# H743ZI_SD_LCD_DRAM_Dev.net
KiCad netlist of a schematic drawn in Altium Designer
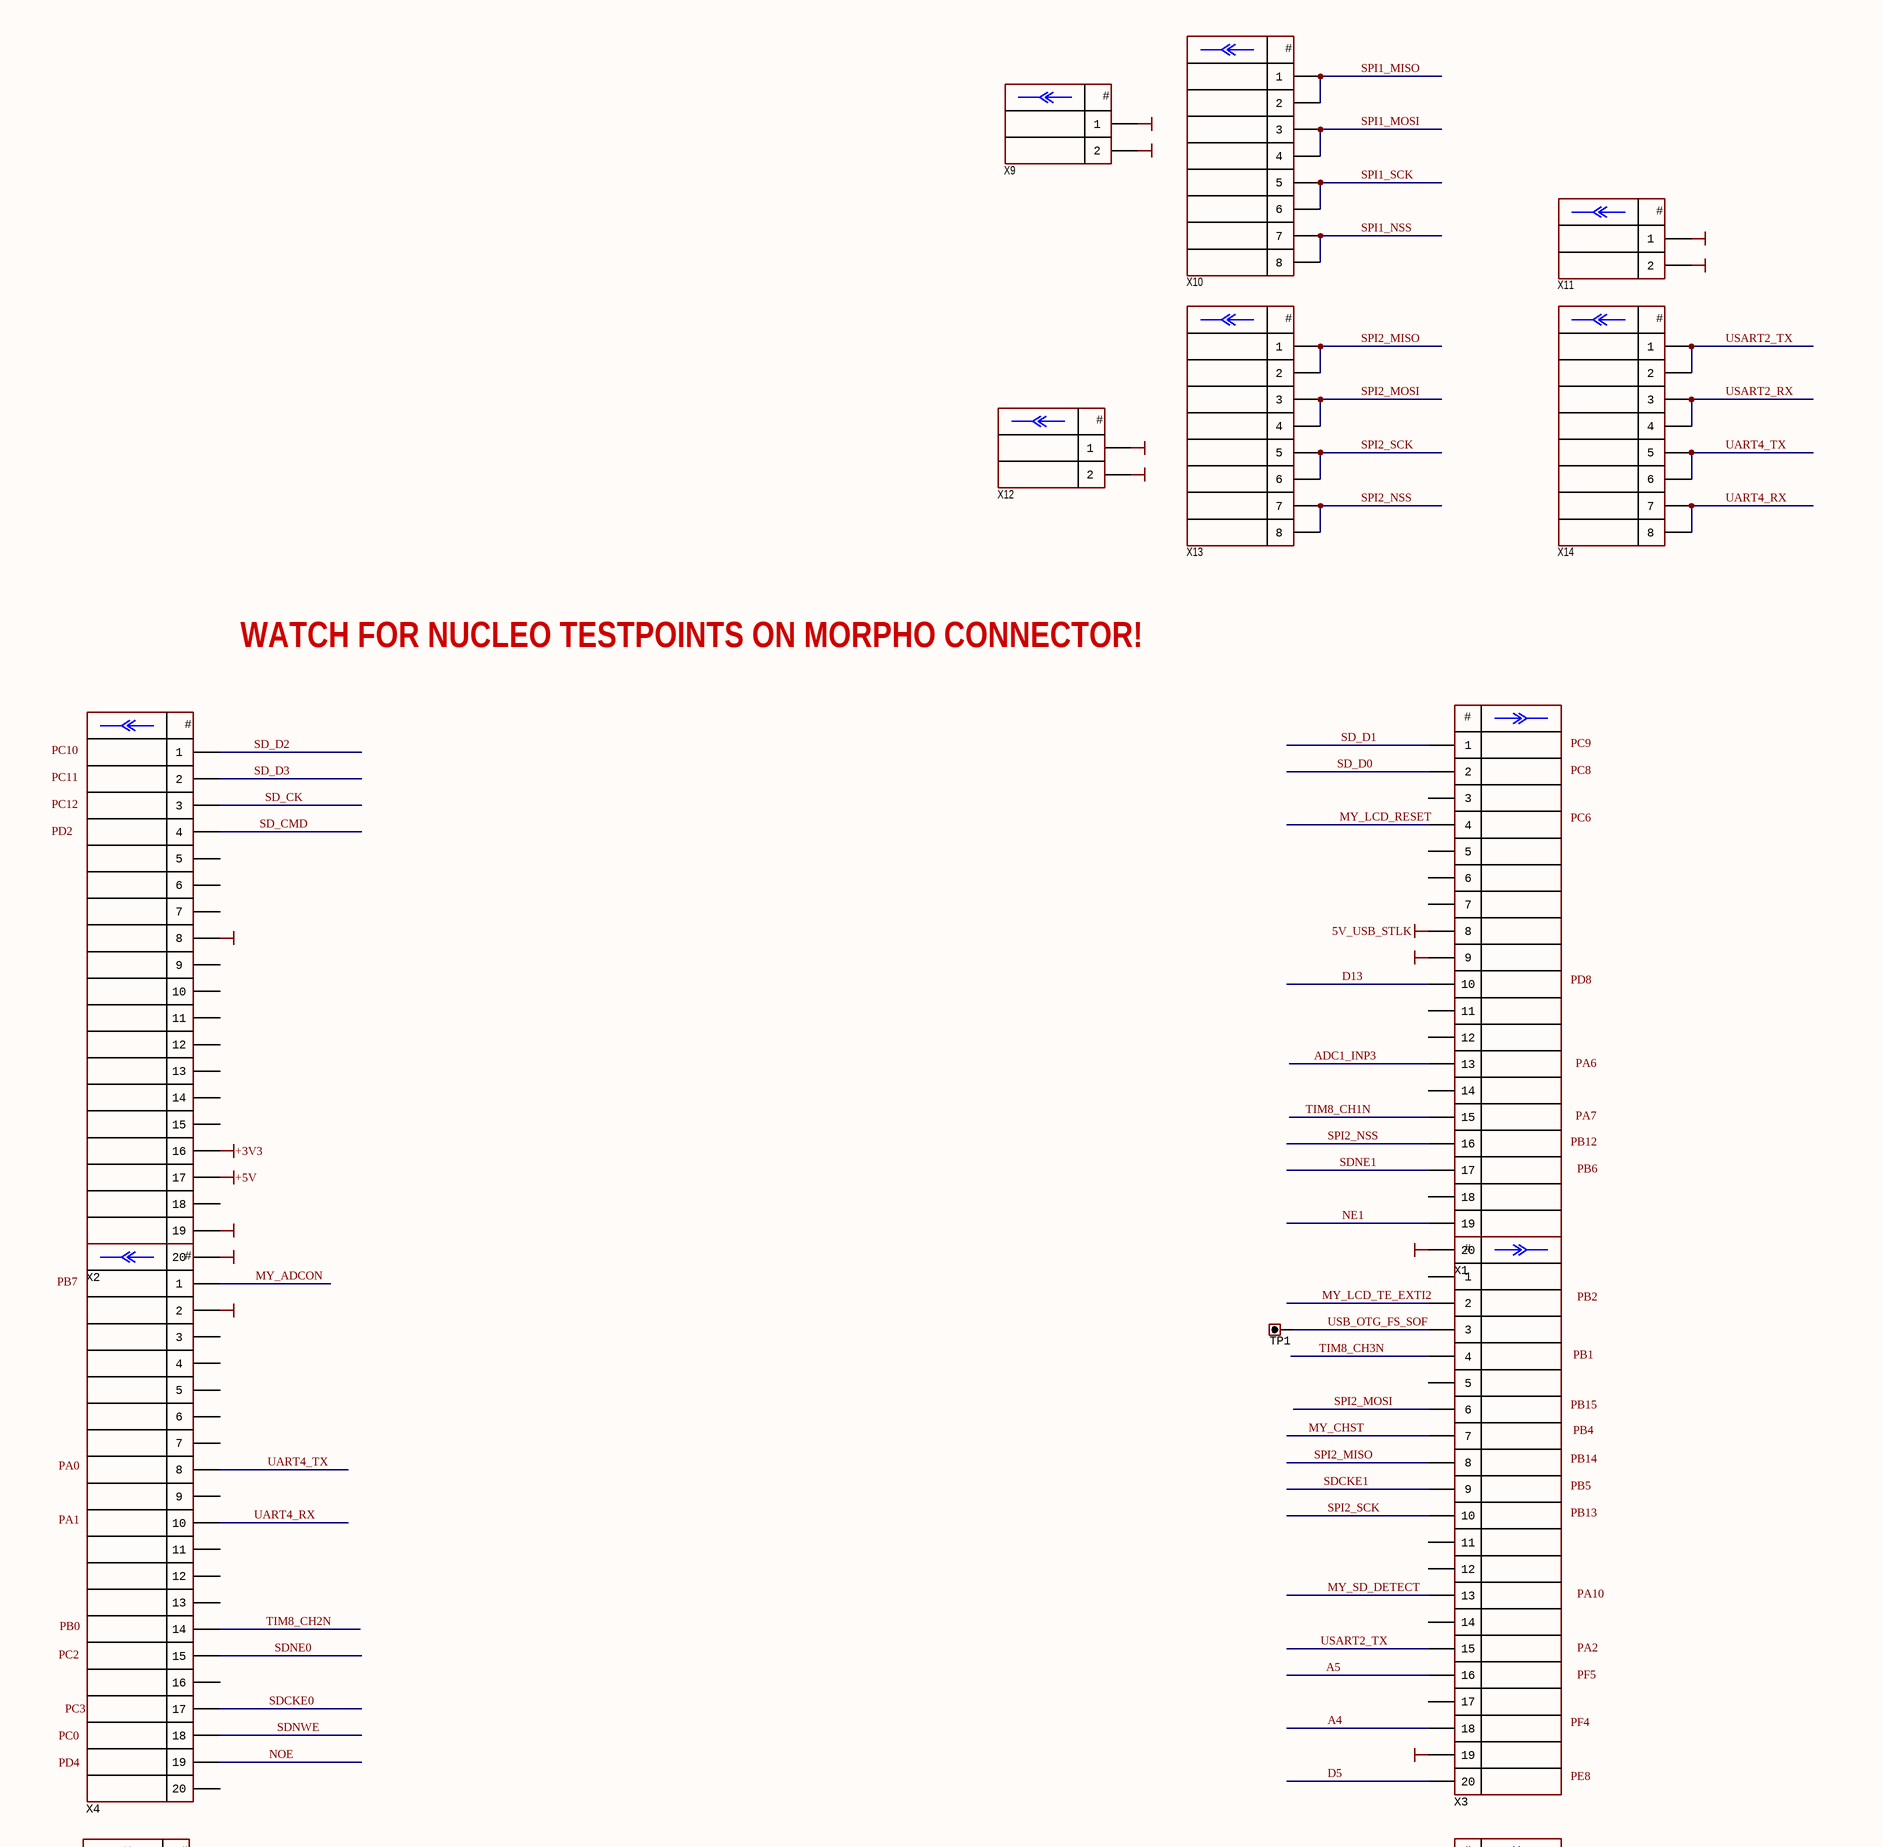
[diagram p0: H743ZI_SD_LCD_DRAM_Dev.SchDoc, top left]
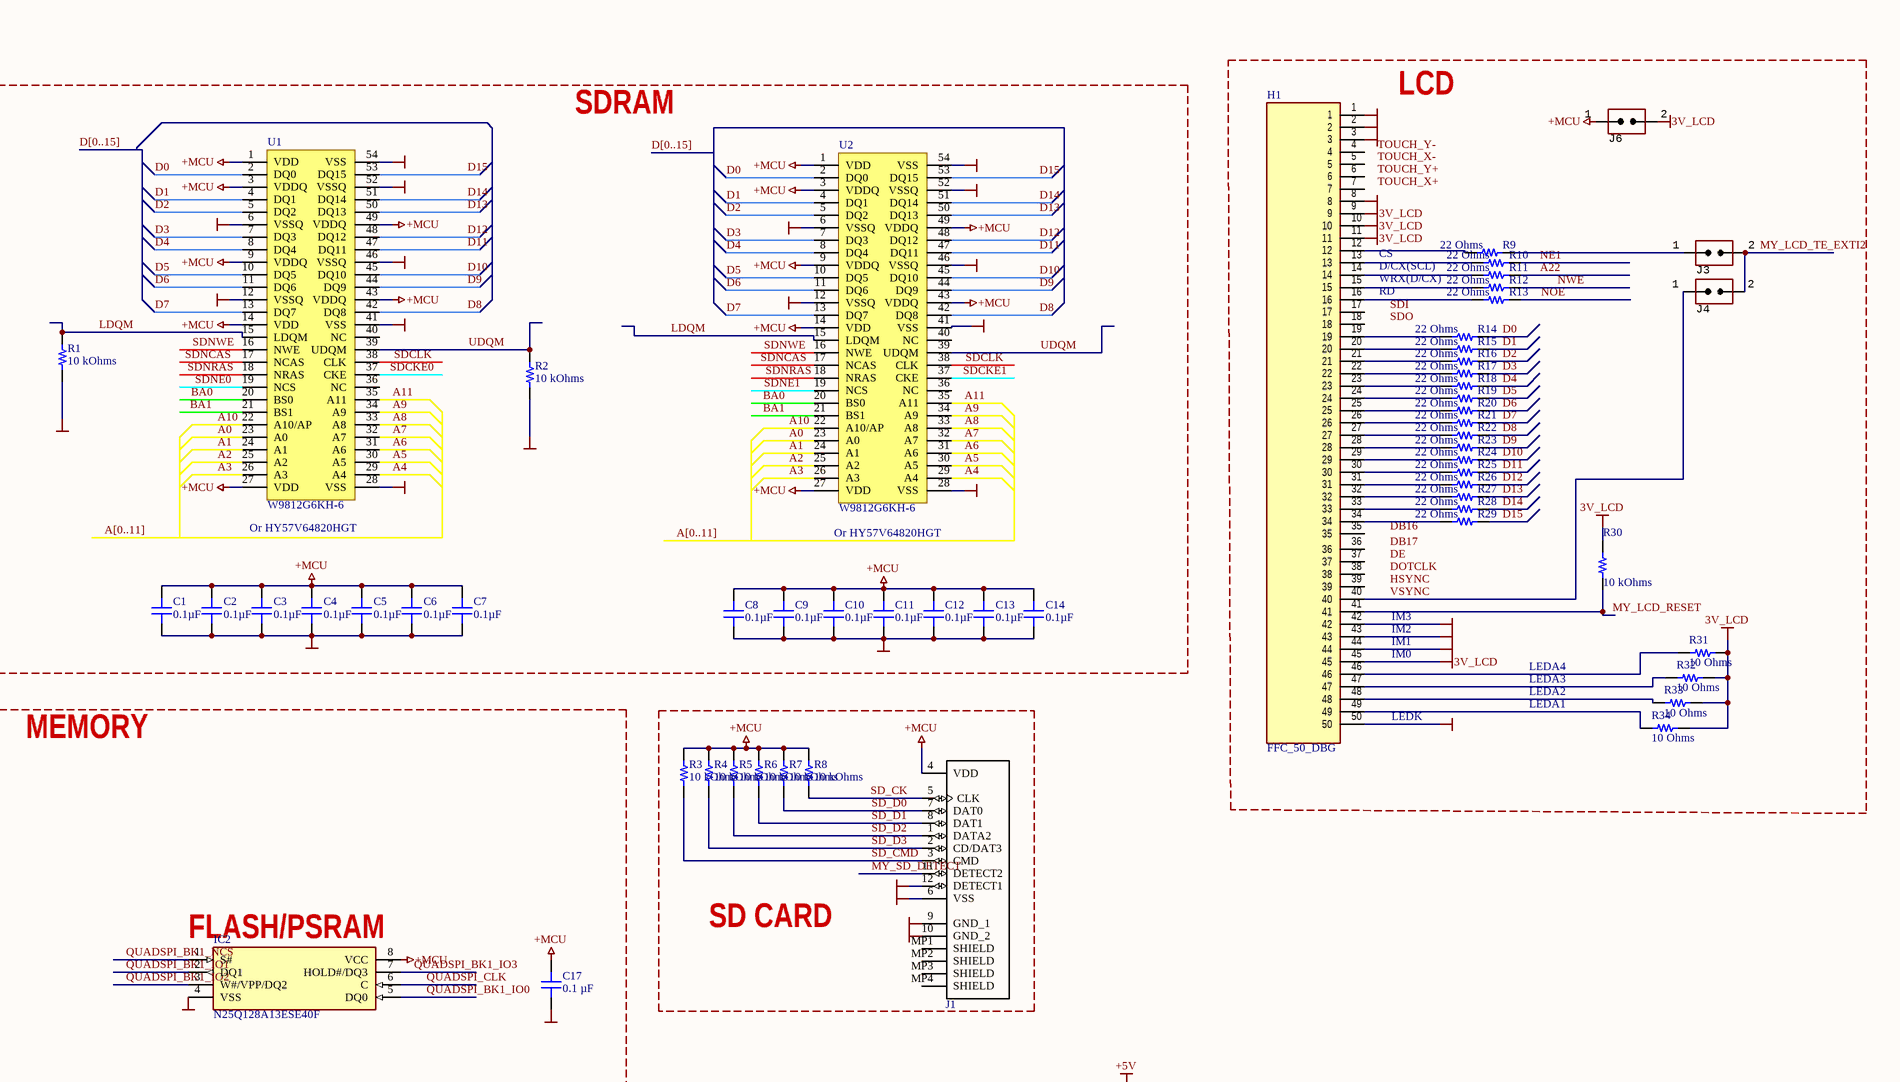
[diagram p1: H743ZI_SD_LCD_DRAM_Dev.SchDoc, top right]
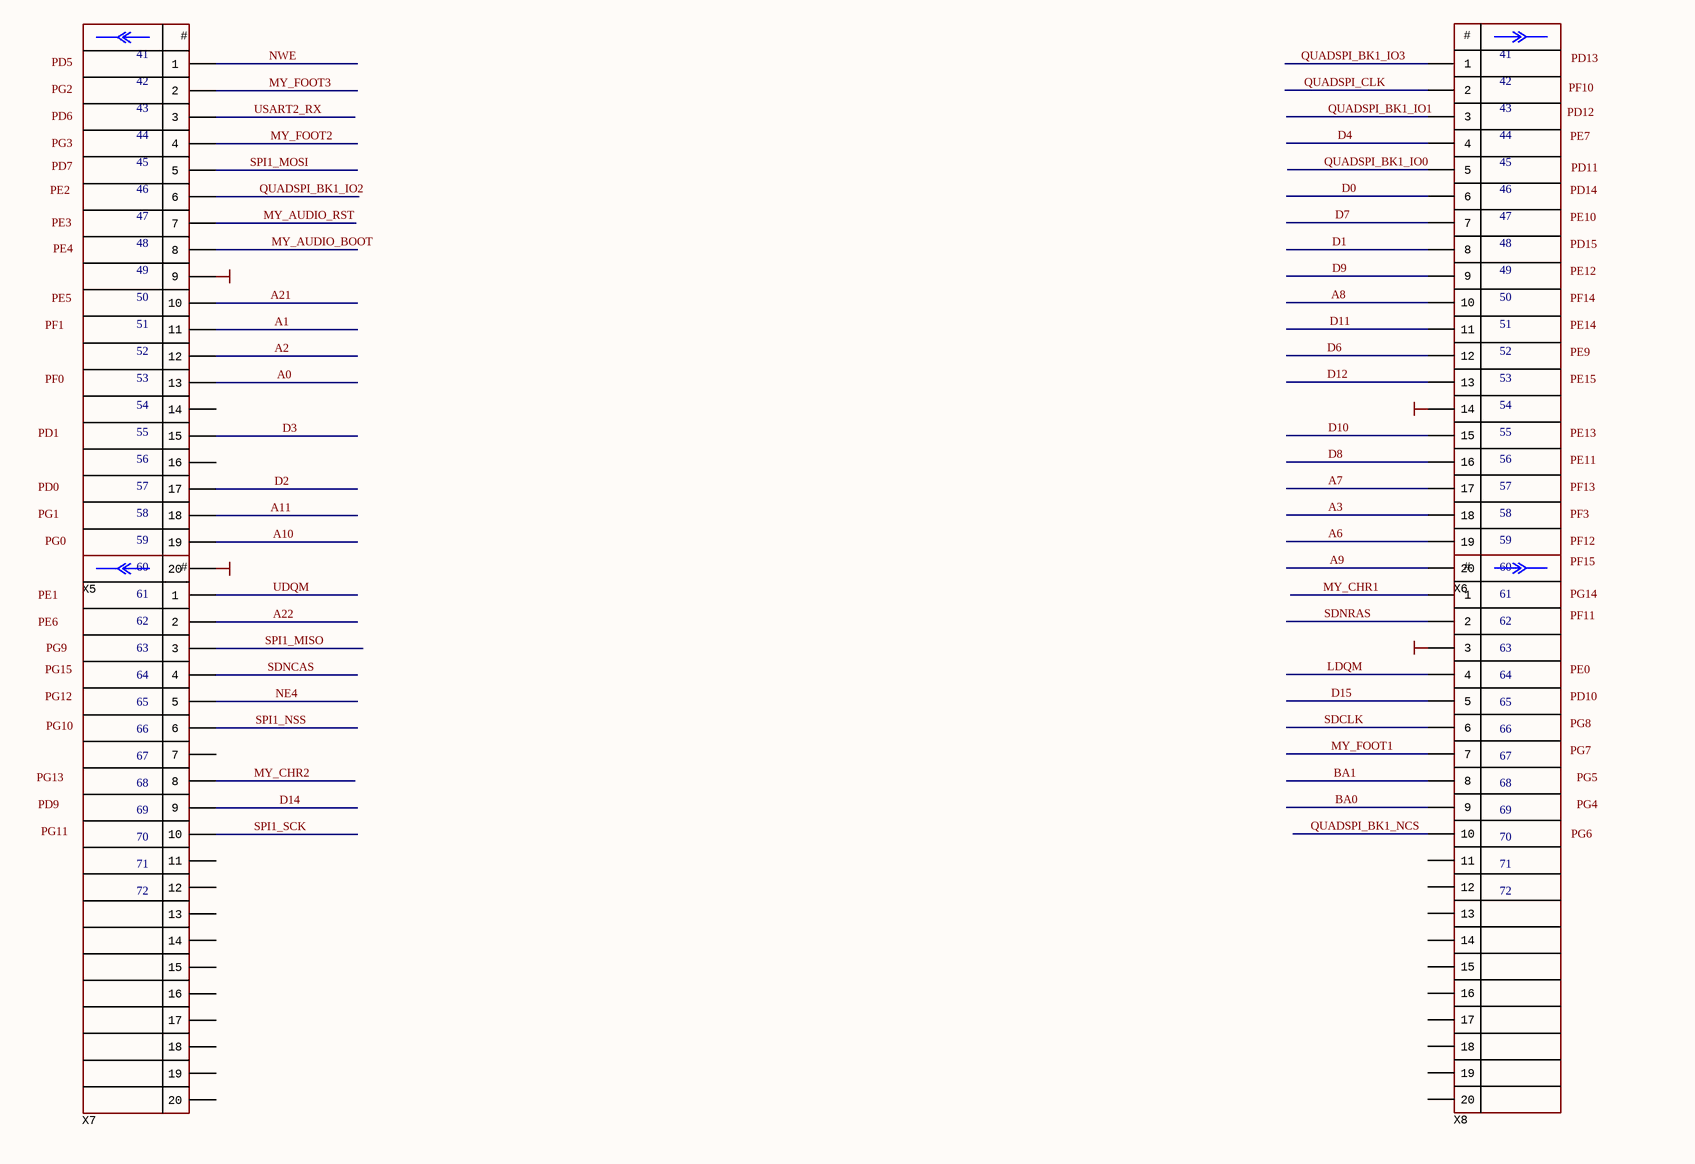
[diagram p2: H743ZI_SD_LCD_DRAM_Dev.SchDoc, bottom left]
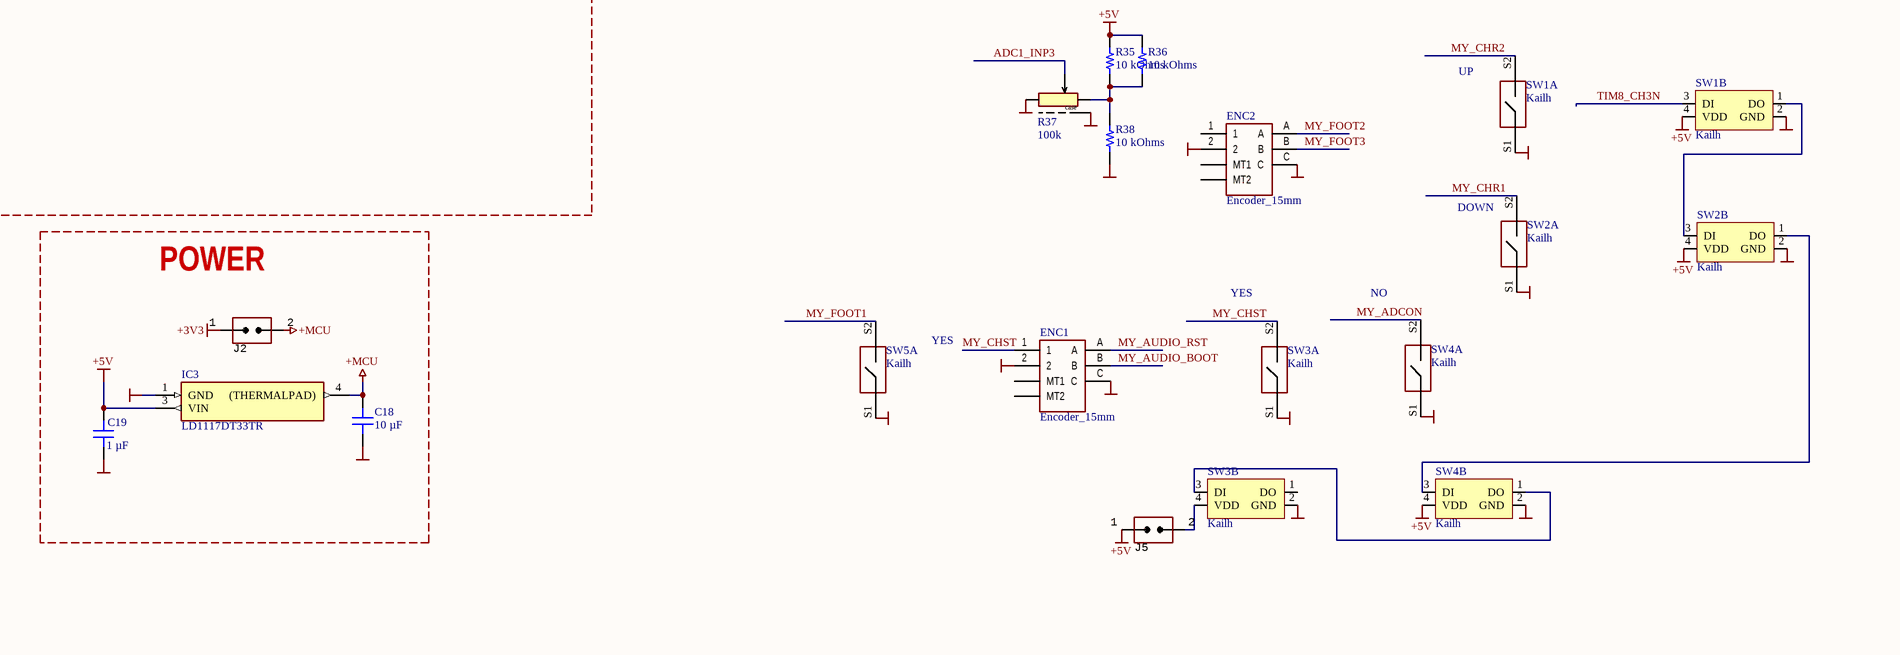
[diagram p3: H743ZI_SD_LCD_DRAM_Dev.SchDoc, bottom right]

(export (version "E")
  (design (tool "Eeschema 10.0.6"))
  (components
    (comp (ref "C1")
      (value "0.1µF")
      (footprint "CAP 0402_1005")
      (description "CAP CER 0.1UF 16V X7R 0402")
      (fields (field (name "PART NUMBER") "C0402C104K4RACAUTO") (field (name "MANUFACTURER") "KEMET"))
      (libsource (lib "Celestial Altium Library - altium_library") (part "Capacitor"))
    )
    (comp (ref "C2")
      (value "0.1µF")
      (footprint "CAP 0402_1005")
      (description "CAP CER 0.1UF 16V X7R 0402")
      (fields (field (name "PART NUMBER") "C0402C104K4RACAUTO") (field (name "MANUFACTURER") "KEMET"))
      (libsource (lib "Celestial Altium Library - altium_library") (part "Capacitor"))
    )
    (comp (ref "C3")
      (value "0.1µF")
      (footprint "CAP 0402_1005")
      (description "CAP CER 0.1UF 16V X7R 0402")
      (fields (field (name "PART NUMBER") "C0402C104K4RACAUTO") (field (name "MANUFACTURER") "KEMET"))
      (libsource (lib "Celestial Altium Library - altium_library") (part "Capacitor"))
    )
    (comp (ref "C4")
      (value "0.1µF")
      (footprint "CAP 0402_1005")
      (description "CAP CER 0.1UF 16V X7R 0402")
      (fields (field (name "PART NUMBER") "C0402C104K4RACAUTO") (field (name "MANUFACTURER") "KEMET"))
      (libsource (lib "Celestial Altium Library - altium_library") (part "Capacitor"))
    )
    (comp (ref "C5")
      (value "0.1µF")
      (footprint "CAP 0402_1005")
      (description "CAP CER 0.1UF 16V X7R 0402")
      (fields (field (name "PART NUMBER") "C0402C104K4RACAUTO") (field (name "MANUFACTURER") "KEMET"))
      (libsource (lib "Celestial Altium Library - altium_library") (part "Capacitor"))
    )
    (comp (ref "C6")
      (value "0.1µF")
      (footprint "CAP 0402_1005")
      (description "CAP CER 0.1UF 16V X7R 0402")
      (fields (field (name "PART NUMBER") "C0402C104K4RACAUTO") (field (name "MANUFACTURER") "KEMET"))
      (libsource (lib "Celestial Altium Library - altium_library") (part "Capacitor"))
    )
    (comp (ref "C7")
      (value "0.1µF")
      (footprint "CAP 0402_1005")
      (description "CAP CER 0.1UF 16V X7R 0402")
      (fields (field (name "PART NUMBER") "C0402C104K4RACAUTO") (field (name "MANUFACTURER") "KEMET"))
      (libsource (lib "Celestial Altium Library - altium_library") (part "Capacitor"))
    )
    (comp (ref "C8")
      (value "0.1µF")
      (footprint "CAP 0402_1005")
      (description "CAP CER 0.1UF 16V X7R 0402")
      (fields (field (name "PART NUMBER") "C0402C104K4RACAUTO") (field (name "MANUFACTURER") "KEMET"))
      (libsource (lib "Celestial Altium Library - altium_library") (part "Capacitor"))
    )
    (comp (ref "C9")
      (value "0.1µF")
      (footprint "CAP 0402_1005")
      (description "CAP CER 0.1UF 16V X7R 0402")
      (fields (field (name "PART NUMBER") "C0402C104K4RACAUTO") (field (name "MANUFACTURER") "KEMET"))
      (libsource (lib "Celestial Altium Library - altium_library") (part "Capacitor"))
    )
    (comp (ref "C10")
      (value "0.1µF")
      (footprint "CAP 0402_1005")
      (description "CAP CER 0.1UF 16V X7R 0402")
      (fields (field (name "PART NUMBER") "C0402C104K4RACAUTO") (field (name "MANUFACTURER") "KEMET"))
      (libsource (lib "Celestial Altium Library - altium_library") (part "Capacitor"))
    )
    (comp (ref "C11")
      (value "0.1µF")
      (footprint "CAP 0402_1005")
      (description "CAP CER 0.1UF 16V X7R 0402")
      (fields (field (name "PART NUMBER") "C0402C104K4RACAUTO") (field (name "MANUFACTURER") "KEMET"))
      (libsource (lib "Celestial Altium Library - altium_library") (part "Capacitor"))
    )
    (comp (ref "C12")
      (value "0.1µF")
      (footprint "CAP 0402_1005")
      (description "CAP CER 0.1UF 16V X7R 0402")
      (fields (field (name "PART NUMBER") "C0402C104K4RACAUTO") (field (name "MANUFACTURER") "KEMET"))
      (libsource (lib "Celestial Altium Library - altium_library") (part "Capacitor"))
    )
    (comp (ref "C13")
      (value "0.1µF")
      (footprint "CAP 0402_1005")
      (description "CAP CER 0.1UF 16V X7R 0402")
      (fields (field (name "PART NUMBER") "C0402C104K4RACAUTO") (field (name "MANUFACTURER") "KEMET"))
      (libsource (lib "Celestial Altium Library - altium_library") (part "Capacitor"))
    )
    (comp (ref "C14")
      (value "0.1µF")
      (footprint "CAP 0402_1005")
      (description "CAP CER 0.1UF 16V X7R 0402")
      (fields (field (name "PART NUMBER") "C0402C104K4RACAUTO") (field (name "MANUFACTURER") "KEMET"))
      (libsource (lib "Celestial Altium Library - altium_library") (part "Capacitor"))
    )
    (comp (ref "C17")
      (value "0.1 µF")
      (footprint "CAP 0603_1608")
      (description "CAP CER 0.1UF 50V X7R 0603")
      (fields (field (name "PART NUMBER") "C0603C104K5RAC7411") (field (name "MANUFACTURER") "KEMET"))
      (libsource (lib "Celestial Altium Library - altium_library") (part "Capacitor"))
    )
    (comp (ref "C18")
      (value "10 µF")
      (footprint "CAP 0805_2012")
      (description "CAP CER 10UF 10V X5R 0805")
      (fields (field (name "PART NUMBER") "C0805C106K8PAC7800") (field (name "MANUFACTURER") "KEMET"))
      (libsource (lib "Celestial Altium Library - altium_library") (part "Capacitor"))
    )
    (comp (ref "C19")
      (value "1 µF")
      (footprint "CAP 0805_2012")
      (description "CAP CER 1UF 16V X7R 0805")
      (fields (field (name "PART NUMBER") "C0805C105K4RAC7800") (field (name "MANUFACTURER") "KEMET"))
      (libsource (lib "Celestial Altium Library - altium_library") (part "Capacitor"))
    )
    (comp (ref "ENC1")
      (value "Encoder_15mm")
      (footprint "ProtoStack_H750VBT:EC11_15mm")
      (libsource (lib "ProtoStack_H750VBT") (part "Encoder_15mm"))
    )
    (comp (ref "ENC2")
      (value "Encoder_15mm")
      (footprint "ProtoStack_H750VBT:EC11_15mm")
      (libsource (lib "ProtoStack_H750VBT") (part "Encoder_15mm"))
    )
    (comp (ref "H1")
      (value "FFC_50_DBG")
      (footprint "ProtoStack_H750VBT:FFC_50_DBG")
      (libsource (lib "ProtoStack_H750VBT") (part "FFC_50_DBG"))
    )
    (comp (ref "IC2")
      (value "N25Q128A13ESE40F")
      (footprint "SOIC127P790X216-8N")
      (description "Integrated Circuit")
      (fields (field (name "MOUSER PART NUMBER") "340-182267"))
      (libsource (lib "ProtoStack_H750VBT") (part "N25Q128A13ESE40F"))
    )
    (comp (ref "IC3")
      (value "LD1117DT33TR")
      (footprint "ProtoStack_H750VBT:TO228P972X240-3N")
      (description "Integrated Circuit")
      (fields (field (name "MOUSER PART NUMBER") "511-LD1117DT33-TR"))
      (libsource (lib "ProtoStack_H750VBT") (part "LD1117DT33TR"))
    )
    (comp (ref "J1")
      (value "SCHA4B0400")
      (footprint "ProtoStack_H750VBT:SCHA4B0400")
      (description "SD card Connector")
      (fields (field (name "MOUSER PART NUMBER") "688-SCHA4B0400"))
      (libsource (lib "ProtoStack_H750VBT") (part "SCHA4B0400"))
    )
    (comp (ref "J2")
      (value "~")
      (footprint "CON: JUMPER x1")
      (libsource (lib "connector") (part "Jumper_single"))
    )
    (comp (ref "J3")
      (value "~")
      (footprint "CON: JUMPER x1")
      (libsource (lib "connector") (part "Jumper_single"))
    )
    (comp (ref "J4")
      (value "~")
      (footprint "CON: JUMPER x1")
      (libsource (lib "connector") (part "Jumper_single"))
    )
    (comp (ref "J5")
      (value "~")
      (footprint "CON: JUMPER x1")
      (libsource (lib "connector") (part "Jumper_single"))
    )
    (comp (ref "J6")
      (value "~")
      (footprint "CON: JUMPER x1")
      (libsource (lib "connector") (part "Jumper_single"))
    )
    (comp (ref "R1")
      (value "10 kOhms")
      (footprint "RES 0603_1608")
      (description "RES SMD 10K OHM 1% 1/10W 0603")
      (fields
        (field (name "PART NUMBER") "ERJ-3EKF1002V")
        (field (name "MANUFACTURER") "Panasonic Electronic Components")
      )
      (libsource (lib "Celestial Altium Library - altium_library") (part "Resistor"))
    )
    (comp (ref "R2")
      (value "10 kOhms")
      (footprint "RES 0603_1608")
      (description "RES SMD 10K OHM 1% 1/10W 0603")
      (fields
        (field (name "PART NUMBER") "ERJ-3EKF1002V")
        (field (name "MANUFACTURER") "Panasonic Electronic Components")
      )
      (libsource (lib "Celestial Altium Library - altium_library") (part "Resistor"))
    )
    (comp (ref "R3")
      (value "10 kOhms")
      (footprint "RES 0603_1608")
      (description "RES SMD 10K OHM 1% 1/10W 0603")
      (fields
        (field (name "PART NUMBER") "ERJ-3EKF1002V")
        (field (name "MANUFACTURER") "Panasonic Electronic Components")
      )
      (libsource (lib "Celestial Altium Library - altium_library") (part "Resistor"))
    )
    (comp (ref "R4")
      (value "10 kOhms")
      (footprint "RES 0603_1608")
      (description "RES SMD 10K OHM 1% 1/10W 0603")
      (fields
        (field (name "PART NUMBER") "ERJ-3EKF1002V")
        (field (name "MANUFACTURER") "Panasonic Electronic Components")
      )
      (libsource (lib "Celestial Altium Library - altium_library") (part "Resistor"))
    )
    (comp (ref "R5")
      (value "10 kOhms")
      (footprint "RES 0603_1608")
      (description "RES SMD 10K OHM 1% 1/10W 0603")
      (fields
        (field (name "PART NUMBER") "ERJ-3EKF1002V")
        (field (name "MANUFACTURER") "Panasonic Electronic Components")
      )
      (libsource (lib "Celestial Altium Library - altium_library") (part "Resistor"))
    )
    (comp (ref "R6")
      (value "10 kOhms")
      (footprint "RES 0603_1608")
      (description "RES SMD 10K OHM 1% 1/10W 0603")
      (fields
        (field (name "PART NUMBER") "ERJ-3EKF1002V")
        (field (name "MANUFACTURER") "Panasonic Electronic Components")
      )
      (libsource (lib "Celestial Altium Library - altium_library") (part "Resistor"))
    )
    (comp (ref "R7")
      (value "10 kOhms")
      (footprint "RES 0603_1608")
      (description "RES SMD 10K OHM 1% 1/10W 0603")
      (fields
        (field (name "PART NUMBER") "ERJ-3EKF1002V")
        (field (name "MANUFACTURER") "Panasonic Electronic Components")
      )
      (libsource (lib "Celestial Altium Library - altium_library") (part "Resistor"))
    )
    (comp (ref "R8")
      (value "10 kOhms")
      (footprint "RES 0603_1608")
      (description "RES SMD 10K OHM 1% 1/10W 0603")
      (fields
        (field (name "PART NUMBER") "ERJ-3EKF1002V")
        (field (name "MANUFACTURER") "Panasonic Electronic Components")
      )
      (libsource (lib "Celestial Altium Library - altium_library") (part "Resistor"))
    )
    (comp (ref "R9")
      (value "22 Ohms")
      (footprint "RES 0402_1005")
      (description "RES 22 OHM 5% 1/16W 0402")
      (fields
        (field (name "PART NUMBER") "RMCF0402JT22R0")
        (field (name "MANUFACTURER") "Stackpole Electronics Inc")
      )
      (libsource (lib "Celestial Altium Library - altium_library") (part "Resistor"))
    )
    (comp (ref "R10")
      (value "22 Ohms")
      (footprint "RES 0402_1005")
      (description "RES 22 OHM 5% 1/16W 0402")
      (fields
        (field (name "PART NUMBER") "RMCF0402JT22R0")
        (field (name "MANUFACTURER") "Stackpole Electronics Inc")
      )
      (libsource (lib "Celestial Altium Library - altium_library") (part "Resistor"))
    )
    (comp (ref "R11")
      (value "22 Ohms")
      (footprint "RES 0402_1005")
      (description "RES 22 OHM 5% 1/16W 0402")
      (fields
        (field (name "PART NUMBER") "RMCF0402JT22R0")
        (field (name "MANUFACTURER") "Stackpole Electronics Inc")
      )
      (libsource (lib "Celestial Altium Library - altium_library") (part "Resistor"))
    )
    (comp (ref "R12")
      (value "22 Ohms")
      (footprint "RES 0402_1005")
      (description "RES 22 OHM 5% 1/16W 0402")
      (fields
        (field (name "PART NUMBER") "RMCF0402JT22R0")
        (field (name "MANUFACTURER") "Stackpole Electronics Inc")
      )
      (libsource (lib "Celestial Altium Library - altium_library") (part "Resistor"))
    )
    (comp (ref "R13")
      (value "22 Ohms")
      (footprint "RES 0402_1005")
      (description "RES 22 OHM 5% 1/16W 0402")
      (fields
        (field (name "PART NUMBER") "RMCF0402JT22R0")
        (field (name "MANUFACTURER") "Stackpole Electronics Inc")
      )
      (libsource (lib "Celestial Altium Library - altium_library") (part "Resistor"))
    )
    (comp (ref "R14")
      (value "22 Ohms")
      (footprint "RES 0402_1005")
      (description "RES 22 OHM 5% 1/16W 0402")
      (fields
        (field (name "PART NUMBER") "RMCF0402JT22R0")
        (field (name "MANUFACTURER") "Stackpole Electronics Inc")
      )
      (libsource (lib "Celestial Altium Library - altium_library") (part "Resistor"))
    )
    (comp (ref "R15")
      (value "22 Ohms")
      (footprint "RES 0402_1005")
      (description "RES 22 OHM 5% 1/16W 0402")
      (fields
        (field (name "PART NUMBER") "RMCF0402JT22R0")
        (field (name "MANUFACTURER") "Stackpole Electronics Inc")
      )
      (libsource (lib "Celestial Altium Library - altium_library") (part "Resistor"))
    )
    (comp (ref "R16")
      (value "22 Ohms")
      (footprint "RES 0402_1005")
      (description "RES 22 OHM 5% 1/16W 0402")
      (fields
        (field (name "PART NUMBER") "RMCF0402JT22R0")
        (field (name "MANUFACTURER") "Stackpole Electronics Inc")
      )
      (libsource (lib "Celestial Altium Library - altium_library") (part "Resistor"))
    )
    (comp (ref "R17")
      (value "22 Ohms")
      (footprint "RES 0402_1005")
      (description "RES 22 OHM 5% 1/16W 0402")
      (fields
        (field (name "PART NUMBER") "RMCF0402JT22R0")
        (field (name "MANUFACTURER") "Stackpole Electronics Inc")
      )
      (libsource (lib "Celestial Altium Library - altium_library") (part "Resistor"))
    )
    (comp (ref "R18")
      (value "22 Ohms")
      (footprint "RES 0402_1005")
      (description "RES 22 OHM 5% 1/16W 0402")
      (fields
        (field (name "PART NUMBER") "RMCF0402JT22R0")
        (field (name "MANUFACTURER") "Stackpole Electronics Inc")
      )
      (libsource (lib "Celestial Altium Library - altium_library") (part "Resistor"))
    )
    (comp (ref "R19")
      (value "22 Ohms")
      (footprint "RES 0402_1005")
      (description "RES 22 OHM 5% 1/16W 0402")
      (fields
        (field (name "PART NUMBER") "RMCF0402JT22R0")
        (field (name "MANUFACTURER") "Stackpole Electronics Inc")
      )
      (libsource (lib "Celestial Altium Library - altium_library") (part "Resistor"))
    )
    (comp (ref "R20")
      (value "22 Ohms")
      (footprint "RES 0402_1005")
      (description "RES 22 OHM 5% 1/16W 0402")
      (fields
        (field (name "PART NUMBER") "RMCF0402JT22R0")
        (field (name "MANUFACTURER") "Stackpole Electronics Inc")
      )
      (libsource (lib "Celestial Altium Library - altium_library") (part "Resistor"))
    )
    (comp (ref "R21")
      (value "22 Ohms")
      (footprint "RES 0402_1005")
      (description "RES 22 OHM 5% 1/16W 0402")
      (fields
        (field (name "PART NUMBER") "RMCF0402JT22R0")
        (field (name "MANUFACTURER") "Stackpole Electronics Inc")
      )
      (libsource (lib "Celestial Altium Library - altium_library") (part "Resistor"))
    )
    (comp (ref "R22")
      (value "22 Ohms")
      (footprint "RES 0402_1005")
      (description "RES 22 OHM 5% 1/16W 0402")
      (fields
        (field (name "PART NUMBER") "RMCF0402JT22R0")
        (field (name "MANUFACTURER") "Stackpole Electronics Inc")
      )
      (libsource (lib "Celestial Altium Library - altium_library") (part "Resistor"))
    )
    (comp (ref "R23")
      (value "22 Ohms")
      (footprint "RES 0402_1005")
      (description "RES 22 OHM 5% 1/16W 0402")
      (fields
        (field (name "PART NUMBER") "RMCF0402JT22R0")
        (field (name "MANUFACTURER") "Stackpole Electronics Inc")
      )
      (libsource (lib "Celestial Altium Library - altium_library") (part "Resistor"))
    )
    (comp (ref "R24")
      (value "22 Ohms")
      (footprint "RES 0402_1005")
      (description "RES 22 OHM 5% 1/16W 0402")
      (fields
        (field (name "PART NUMBER") "RMCF0402JT22R0")
        (field (name "MANUFACTURER") "Stackpole Electronics Inc")
      )
      (libsource (lib "Celestial Altium Library - altium_library") (part "Resistor"))
    )
    (comp (ref "R25")
      (value "22 Ohms")
      (footprint "RES 0402_1005")
      (description "RES 22 OHM 5% 1/16W 0402")
      (fields
        (field (name "PART NUMBER") "RMCF0402JT22R0")
        (field (name "MANUFACTURER") "Stackpole Electronics Inc")
      )
      (libsource (lib "Celestial Altium Library - altium_library") (part "Resistor"))
    )
    (comp (ref "R26")
      (value "22 Ohms")
      (footprint "RES 0402_1005")
      (description "RES 22 OHM 5% 1/16W 0402")
      (fields
        (field (name "PART NUMBER") "RMCF0402JT22R0")
        (field (name "MANUFACTURER") "Stackpole Electronics Inc")
      )
      (libsource (lib "Celestial Altium Library - altium_library") (part "Resistor"))
    )
    (comp (ref "R27")
      (value "22 Ohms")
      (footprint "RES 0402_1005")
      (description "RES 22 OHM 5% 1/16W 0402")
      (fields
        (field (name "PART NUMBER") "RMCF0402JT22R0")
        (field (name "MANUFACTURER") "Stackpole Electronics Inc")
      )
      (libsource (lib "Celestial Altium Library - altium_library") (part "Resistor"))
    )
    (comp (ref "R28")
      (value "22 Ohms")
      (footprint "RES 0402_1005")
      (description "RES 22 OHM 5% 1/16W 0402")
      (fields
        (field (name "PART NUMBER") "RMCF0402JT22R0")
        (field (name "MANUFACTURER") "Stackpole Electronics Inc")
      )
      (libsource (lib "Celestial Altium Library - altium_library") (part "Resistor"))
    )
    (comp (ref "R29")
      (value "22 Ohms")
      (footprint "RES 0402_1005")
      (description "RES 22 OHM 5% 1/16W 0402")
      (fields
        (field (name "PART NUMBER") "RMCF0402JT22R0")
        (field (name "MANUFACTURER") "Stackpole Electronics Inc")
      )
      (libsource (lib "Celestial Altium Library - altium_library") (part "Resistor"))
    )
    (comp (ref "R30")
      (value "10 kOhms")
      (footprint "RES 0603_1608")
      (description "RES SMD 10K OHM 1% 1/10W 0603")
      (fields
        (field (name "PART NUMBER") "ERJ-3EKF1002V")
        (field (name "MANUFACTURER") "Panasonic Electronic Components")
      )
      (libsource (lib "Celestial Altium Library - altium_library") (part "Resistor"))
    )
    (comp (ref "R31")
      (value "10 Ohms")
      (footprint "RES 0603_1608")
      (description "RES SMD 10 OHM 1% 1/3W 0603")
      (fields
        (field (name "PART NUMBER") "ERJ-PA3F10R0V")
        (field (name "MANUFACTURER") "Panasonic Electronic Components")
      )
      (libsource (lib "Celestial Altium Library - altium_library") (part "Resistor"))
    )
    (comp (ref "R32")
      (value "10 Ohms")
      (footprint "RES 0603_1608")
      (description "RES SMD 10 OHM 1% 1/3W 0603")
      (fields
        (field (name "PART NUMBER") "ERJ-PA3F10R0V")
        (field (name "MANUFACTURER") "Panasonic Electronic Components")
      )
      (libsource (lib "Celestial Altium Library - altium_library") (part "Resistor"))
    )
    (comp (ref "R33")
      (value "10 Ohms")
      (footprint "RES 0603_1608")
      (description "RES SMD 10 OHM 1% 1/3W 0603")
      (fields
        (field (name "PART NUMBER") "ERJ-PA3F10R0V")
        (field (name "MANUFACTURER") "Panasonic Electronic Components")
      )
      (libsource (lib "Celestial Altium Library - altium_library") (part "Resistor"))
    )
    (comp (ref "R34")
      (value "10 Ohms")
      (footprint "RES 0603_1608")
      (description "RES SMD 10 OHM 1% 1/3W 0603")
      (fields
        (field (name "PART NUMBER") "ERJ-PA3F10R0V")
        (field (name "MANUFACTURER") "Panasonic Electronic Components")
      )
      (libsource (lib "Celestial Altium Library - altium_library") (part "Resistor"))
    )
    (comp (ref "R35")
      (value "10 kOhms")
      (footprint "RES 0603_1608")
      (description "RES SMD 10K OHM 1% 1/10W 0603")
      (fields (field (name "PART NUMBER") "ERJ-3EKF1002V"))
      (libsource (lib "Celestial Altium Library - altium_library") (part "Resistor"))
    )
    (comp (ref "R36")
      (value "10 kOhms")
      (footprint "RES 0603_1608")
      (description "RES SMD 10K OHM 1% 1/10W 0603")
      (fields (field (name "PART NUMBER") "ERJ-3EKF1002V"))
      (libsource (lib "Celestial Altium Library - altium_library") (part "Resistor"))
    )
    (comp (ref "R37") (value "100k") (footprint "POT") (libsource (lib "Analog") (part "POT 9MM 100K")))
    (comp (ref "R38")
      (value "10 kOhms")
      (footprint "RES 0603_1608")
      (description "RES SMD 10K OHM 1% 1/10W 0603")
      (fields (field (name "PART NUMBER") "ERJ-3EKF1002V"))
      (libsource (lib "Celestial Altium Library - altium_library") (part "Resistor"))
    )
    (comp (ref "SW1")
      (value "Kailh")
      (footprint "ProtoStack_H750VBT:KAILH_UNI_MX_WS2812")
      (description "Kailh keyboard switch, hotswap rgb, dual-side hotswap options + low prifile variant")
      (libsource (lib "ProtoStack_H750VBT") (part "Kailh_hotswap_WS2812"))
    )
    (comp (ref "SW2")
      (value "Kailh")
      (footprint "ProtoStack_H750VBT:KAILH_UNI_MX_WS2812")
      (description "Kailh keyboard switch, hotswap rgb, dual-side hotswap options + low prifile variant")
      (libsource (lib "ProtoStack_H750VBT") (part "Kailh_hotswap_WS2812"))
    )
    (comp (ref "SW3")
      (value "Kailh")
      (footprint "ProtoStack_H750VBT:KAILH_UNI_MX_WS2812")
      (description "Kailh keyboard switch, hotswap rgb, dual-side hotswap options + low prifile variant")
      (libsource (lib "ProtoStack_H750VBT") (part "Kailh_hotswap_WS2812"))
    )
    (comp (ref "SW4")
      (value "Kailh")
      (footprint "ProtoStack_H750VBT:KAILH_UNI_MX_WS2812")
      (description "Kailh keyboard switch, hotswap rgb, dual-side hotswap options + low prifile variant")
      (libsource (lib "ProtoStack_H750VBT") (part "Kailh_hotswap_WS2812"))
    )
    (comp (ref "SW5")
      (value "Kailh")
      (footprint "ProtoStack_H750VBT:KAILH_UNI_MX_WS2812")
      (description "Kailh keyboard switch, hotswap rgb, dual-side hotswap options + low prifile variant")
      (libsource (lib "ProtoStack_H750VBT") (part "Kailh_hotswap_WS2812"))
    )
    (comp (ref "TP1")
      (value "~")
      (footprint "CON: 5116 (Keystone)")
      (fields
        (field (name "MANUFACTURER") "Keystone")
        (field (name "VALUEMANUFACTURERPARTNUMBER") "Test point, Keystone, 5001")
        (field (name "PARTNUMBER") "5001")
      )
      (libsource (lib "connector") (part "Connector_Test_Point"))
    )
    (comp (ref "U1")
      (value "W9812G6KH-6")
      (footprint "TSOP-54")
      (libsource (lib "DAC_ADC") (part "W9812G6KH-6"))
    )
    (comp (ref "U2")
      (value "W9812G6KH-6")
      (footprint "TSOP-54")
      (libsource (lib "DAC_ADC") (part "W9812G6KH-6"))
    )
    (comp (ref "X1")
      (value "~")
      (footprint "CON: PBD-20")
      (fields
        (field (name "MANUFACTURER") "Connfly")
        (field (name "VALUEMANUFACTURERPARTNUMBER") "Connector, 20pin, 2.54mm, 500VAC, 3A")
        (field (name "PARTNUMBER") "PBD-20")
      )
      (libsource (lib "connector") (part "PBD-20"))
    )
    (comp (ref "X2")
      (value "~")
      (footprint "CON: PBD-20")
      (fields
        (field (name "MANUFACTURER") "Connfly")
        (field (name "VALUEMANUFACTURERPARTNUMBER") "Connector, 20pin, 2.54mm, 500VAC, 3A")
        (field (name "PARTNUMBER") "PBD-20")
      )
      (libsource (lib "") (part "PBD-20_1"))
    )
    (comp (ref "X3")
      (value "~")
      (footprint "CON: PBD-20")
      (fields
        (field (name "MANUFACTURER") "Connfly")
        (field (name "VALUEMANUFACTURERPARTNUMBER") "Connector, 20pin, 2.54mm, 500VAC, 3A")
        (field (name "PARTNUMBER") "PBD-20")
      )
      (libsource (lib "connector") (part "PBD-20"))
    )
    (comp (ref "X4")
      (value "~")
      (footprint "CON: PBD-20")
      (fields
        (field (name "MANUFACTURER") "Connfly")
        (field (name "VALUEMANUFACTURERPARTNUMBER") "Connector, 20pin, 2.54mm, 500VAC, 3A")
        (field (name "PARTNUMBER") "PBD-20")
      )
      (libsource (lib "") (part "PBD-20_1"))
    )
    (comp (ref "X5")
      (value "~")
      (footprint "CON: PBD-20")
      (fields
        (field (name "MANUFACTURER") "Connfly")
        (field (name "VALUEMANUFACTURERPARTNUMBER") "Connector, 20pin, 2.54mm, 500VAC, 3A")
        (field (name "PARTNUMBER") "PBD-20")
      )
      (libsource (lib "") (part "PBD-20_1"))
    )
    (comp (ref "X6")
      (value "~")
      (footprint "CON: PBD-20")
      (fields
        (field (name "MANUFACTURER") "Connfly")
        (field (name "VALUEMANUFACTURERPARTNUMBER") "Connector, 20pin, 2.54mm, 500VAC, 3A")
        (field (name "PARTNUMBER") "PBD-20")
      )
      (libsource (lib "connector") (part "PBD-20"))
    )
    (comp (ref "X7")
      (value "~")
      (footprint "CON: PBD-20")
      (fields
        (field (name "MANUFACTURER") "Connfly")
        (field (name "VALUEMANUFACTURERPARTNUMBER") "Connector, 20pin, 2.54mm, 500VAC, 3A")
        (field (name "PARTNUMBER") "PBD-20")
      )
      (libsource (lib "") (part "PBD-20_1"))
    )
    (comp (ref "X8")
      (value "~")
      (footprint "CON: PBD-20")
      (fields
        (field (name "MANUFACTURER") "Connfly")
        (field (name "VALUEMANUFACTURERPARTNUMBER") "Connector, 20pin, 2.54mm, 500VAC, 3A")
        (field (name "PARTNUMBER") "PBD-20")
      )
      (libsource (lib "connector") (part "PBD-20"))
    )
    (comp (ref "X9")
      (value "~")
      (footprint "CON: PLS-2")
      (fields
        (field (name "MANUFACTURER") "Connfly")
        (field (name "VALUEMANUFACTURERPARTNUMBER") "Connector, 2pin, 2.54mm, 500VAC, 3A")
        (field (name "PARTNUMBER") "PLS-2")
      )
      (libsource (lib "connector") (part "PLS-2"))
    )
    (comp (ref "X10")
      (value "~")
      (footprint "CON: PLD-8")
      (fields
        (field (name "MANUFACTURER") "Connfly")
        (field (name "VALUEMANUFACTURERPARTNUMBER") "Connector, 8pin, 2.54mm, 500VAC, 3A")
        (field (name "PARTNUMBER") "PLD-8")
      )
      (libsource (lib "connector") (part "PLD-8"))
    )
    (comp (ref "X11")
      (value "~")
      (footprint "CON: PLS-2")
      (fields
        (field (name "MANUFACTURER") "Connfly")
        (field (name "VALUEMANUFACTURERPARTNUMBER") "Connector, 2pin, 2.54mm, 500VAC, 3A")
        (field (name "PARTNUMBER") "PLS-2")
      )
      (libsource (lib "connector") (part "PLS-2"))
    )
    (comp (ref "X12")
      (value "~")
      (footprint "CON: PLS-2")
      (fields
        (field (name "MANUFACTURER") "Connfly")
        (field (name "VALUEMANUFACTURERPARTNUMBER") "Connector, 2pin, 2.54mm, 500VAC, 3A")
        (field (name "PARTNUMBER") "PLS-2")
      )
      (libsource (lib "connector") (part "PLS-2"))
    )
    (comp (ref "X13")
      (value "~")
      (footprint "CON: PLD-8")
      (fields
        (field (name "MANUFACTURER") "Connfly")
        (field (name "VALUEMANUFACTURERPARTNUMBER") "Connector, 8pin, 2.54mm, 500VAC, 3A")
        (field (name "PARTNUMBER") "PLD-8")
      )
      (libsource (lib "connector") (part "PLD-8"))
    )
    (comp (ref "X14")
      (value "~")
      (footprint "CON: PLD-8")
      (fields
        (field (name "MANUFACTURER") "Connfly")
        (field (name "VALUEMANUFACTURERPARTNUMBER") "Connector, 8pin, 2.54mm, 500VAC, 3A")
        (field (name "PARTNUMBER") "PLD-8")
      )
      (libsource (lib "connector") (part "PLD-8"))
    )
  )
  (nets
    (net (code "1") (name "+3V3") (class "Default")
      (node (ref "J2") (pin "1") (pinfunction "IN_1") (pintype "passive"))
      (node (ref "X2") (pin "16") (pinfunction "16_16") (pintype "power_in"))
    )
    (net (code "2") (name "+5V") (class "Default")
      (node (ref "C19") (pin "2") (pinfunction "2_2") (pintype "passive"))
      (node (ref "IC3") (pin "3") (pinfunction "VIN_3") (pintype "output"))
      (node (ref "J5") (pin "1") (pinfunction "IN_1") (pintype "passive"))
      (node (ref "R35") (pin "2") (pinfunction "2_2") (pintype "passive"))
      (node (ref "R36") (pin "2") (pinfunction "2_2") (pintype "passive"))
      (node (ref "SW1") (pin "4") (pinfunction "VDD_4") (pintype "passive"))
      (node (ref "SW2") (pin "4") (pinfunction "VDD_4") (pintype "passive"))
      (node (ref "SW4") (pin "4") (pinfunction "VDD_4") (pintype "passive"))
      (node (ref "X2") (pin "17") (pinfunction "17_17") (pintype "power_in"))
    )
    (net (code "3") (name "+MCU") (class "Default")
      (node (ref "C1") (pin "1") (pinfunction "1_1") (pintype "passive"))
      (node (ref "C10") (pin "1") (pinfunction "1_1") (pintype "passive"))
      (node (ref "C11") (pin "1") (pinfunction "1_1") (pintype "passive"))
      (node (ref "C12") (pin "1") (pinfunction "1_1") (pintype "passive"))
      (node (ref "C13") (pin "1") (pinfunction "1_1") (pintype "passive"))
      (node (ref "C14") (pin "1") (pinfunction "1_1") (pintype "passive"))
      (node (ref "C17") (pin "2") (pinfunction "2_2") (pintype "passive"))
      (node (ref "C18") (pin "2") (pinfunction "2_2") (pintype "passive"))
      (node (ref "C2") (pin "1") (pinfunction "1_1") (pintype "passive"))
      (node (ref "C3") (pin "1") (pinfunction "1_1") (pintype "passive"))
      (node (ref "C4") (pin "1") (pinfunction "1_1") (pintype "passive"))
      (node (ref "C5") (pin "1") (pinfunction "1_1") (pintype "passive"))
      (node (ref "C6") (pin "1") (pinfunction "1_1") (pintype "passive"))
      (node (ref "C7") (pin "1") (pinfunction "1_1") (pintype "passive"))
      (node (ref "C8") (pin "1") (pinfunction "1_1") (pintype "passive"))
      (node (ref "C9") (pin "1") (pinfunction "1_1") (pintype "passive"))
      (node (ref "IC2") (pin "8") (pinfunction "VCC_8") (pintype "power_in"))
      (node (ref "IC3") (pin "4") (pinfunction "(THERMALPAD)_4") (pintype "output"))
      (node (ref "J1") (pin "4") (pinfunction "VDD_4") (pintype "power_in"))
      (node (ref "J2") (pin "2") (pinfunction "IN_2") (pintype "passive"))
      (node (ref "J6") (pin "1") (pinfunction "IN_1") (pintype "passive"))
      (node (ref "R3") (pin "2") (pinfunction "2_2") (pintype "passive"))
      (node (ref "R4") (pin "2") (pinfunction "2_2") (pintype "passive"))
      (node (ref "R5") (pin "2") (pinfunction "2_2") (pintype "passive"))
      (node (ref "R6") (pin "2") (pinfunction "2_2") (pintype "passive"))
      (node (ref "R7") (pin "2") (pinfunction "2_2") (pintype "passive"))
      (node (ref "R8") (pin "2") (pinfunction "2_2") (pintype "passive"))
      (node (ref "U1") (pin "1") (pinfunction "VDD_1") (pintype "passive"))
      (node (ref "U1") (pin "14") (pinfunction "VDD_14") (pintype "passive"))
      (node (ref "U1") (pin "27") (pinfunction "VDD_27") (pintype "passive"))
      (node (ref "U1") (pin "3") (pinfunction "VDDQ_3") (pintype "passive"))
      (node (ref "U1") (pin "43") (pinfunction "VDDQ_43") (pintype "passive"))
      (node (ref "U1") (pin "49") (pinfunction "VDDQ_49") (pintype "passive"))
      (node (ref "U1") (pin "9") (pinfunction "VDDQ_9") (pintype "passive"))
      (node (ref "U2") (pin "1") (pinfunction "VDD_1") (pintype "passive"))
      (node (ref "U2") (pin "14") (pinfunction "VDD_14") (pintype "passive"))
      (node (ref "U2") (pin "27") (pinfunction "VDD_27") (pintype "passive"))
      (node (ref "U2") (pin "3") (pinfunction "VDDQ_3") (pintype "passive"))
      (node (ref "U2") (pin "43") (pinfunction "VDDQ_43") (pintype "passive"))
      (node (ref "U2") (pin "49") (pinfunction "VDDQ_49") (pintype "passive"))
      (node (ref "U2") (pin "9") (pinfunction "VDDQ_9") (pintype "passive"))
    )
    (net (code "4") (name "/A0") (class "Default")
      (node (ref "U1") (pin "23") (pinfunction "A0_23") (pintype "passive"))
      (node (ref "U2") (pin "23") (pinfunction "A0_23") (pintype "passive"))
      (node (ref "X5") (pin "13") (pinfunction "13_13") (pintype "power_in"))
    )
    (net (code "5") (name "/A1") (class "Default")
      (node (ref "U1") (pin "24") (pinfunction "A1_24") (pintype "passive"))
      (node (ref "U2") (pin "24") (pinfunction "A1_24") (pintype "passive"))
      (node (ref "X5") (pin "11") (pinfunction "11_11") (pintype "power_in"))
    )
    (net (code "6") (name "/A2") (class "Default")
      (node (ref "U1") (pin "25") (pinfunction "A2_25") (pintype "passive"))
      (node (ref "U2") (pin "25") (pinfunction "A2_25") (pintype "passive"))
      (node (ref "X5") (pin "12") (pinfunction "12_12") (pintype "power_in"))
    )
    (net (code "7") (name "/A3") (class "Default")
      (node (ref "U1") (pin "26") (pinfunction "A3_26") (pintype "passive"))
      (node (ref "U2") (pin "26") (pinfunction "A3_26") (pintype "passive"))
      (node (ref "X6") (pin "18") (pinfunction "18_18") (pintype "power_in"))
    )
    (net (code "8") (name "/A4") (class "Default")
      (node (ref "U1") (pin "29") (pinfunction "A4_29") (pintype "passive"))
      (node (ref "U2") (pin "29") (pinfunction "A4_29") (pintype "passive"))
      (node (ref "X3") (pin "18") (pinfunction "18_18") (pintype "power_in"))
    )
    (net (code "9") (name "/A5") (class "Default")
      (node (ref "U1") (pin "30") (pinfunction "A5_30") (pintype "passive"))
      (node (ref "U2") (pin "30") (pinfunction "A5_30") (pintype "passive"))
      (node (ref "X3") (pin "16") (pinfunction "16_16") (pintype "power_in"))
    )
    (net (code "10") (name "/A6") (class "Default")
      (node (ref "U1") (pin "31") (pinfunction "A6_31") (pintype "passive"))
      (node (ref "U2") (pin "31") (pinfunction "A6_31") (pintype "passive"))
      (node (ref "X6") (pin "19") (pinfunction "19_19") (pintype "power_in"))
    )
    (net (code "11") (name "/A7") (class "Default")
      (node (ref "U1") (pin "32") (pinfunction "A7_32") (pintype "passive"))
      (node (ref "U2") (pin "32") (pinfunction "A7_32") (pintype "passive"))
      (node (ref "X6") (pin "17") (pinfunction "17_17") (pintype "power_in"))
    )
    (net (code "12") (name "/A8") (class "Default")
      (node (ref "U1") (pin "33") (pinfunction "A8_33") (pintype "passive"))
      (node (ref "U2") (pin "33") (pinfunction "A8_33") (pintype "passive"))
      (node (ref "X6") (pin "10") (pinfunction "10_10") (pintype "power_in"))
    )
    (net (code "13") (name "/A9") (class "Default")
      (node (ref "U1") (pin "34") (pinfunction "A9_34") (pintype "passive"))
      (node (ref "U2") (pin "34") (pinfunction "A9_34") (pintype "passive"))
      (node (ref "X6") (pin "20") (pinfunction "20_20") (pintype "power_in"))
    )
    (net (code "14") (name "/A10") (class "Default")
      (node (ref "U1") (pin "22") (pinfunction "A10/AP_22") (pintype "passive"))
      (node (ref "U2") (pin "22") (pinfunction "A10/AP_22") (pintype "passive"))
      (node (ref "X5") (pin "19") (pinfunction "19_19") (pintype "power_in"))
    )
    (net (code "15") (name "/A11") (class "Default")
      (node (ref "U1") (pin "35") (pinfunction "A11_35") (pintype "passive"))
      (node (ref "U2") (pin "35") (pinfunction "A11_35") (pintype "passive"))
      (node (ref "X5") (pin "18") (pinfunction "18_18") (pintype "power_in"))
    )
    (net (code "16") (name "/A21") (class "Default")
      (node (ref "X5") (pin "10") (pinfunction "10_10") (pintype "power_in"))
    )
    (net (code "17") (name "/A22") (class "Default")
      (node (ref "R11") (pin "2") (pinfunction "2_2") (pintype "passive"))
      (node (ref "X7") (pin "2") (pinfunction "2_2") (pintype "passive"))
    )
    (net (code "18") (name "/ADC1_INP3") (class "Default")
      (node (ref "R37") (pin "2") (pinfunction "2_2") (pintype "passive"))
      (node (ref "X1") (pin "13") (pinfunction "13_13") (pintype "power_in"))
    )
    (net (code "20") (name "/BA0") (class "Default")
      (node (ref "U1") (pin "20") (pinfunction "BS0_20") (pintype "passive"))
      (node (ref "U2") (pin "20") (pinfunction "BS0_20") (pintype "passive"))
      (node (ref "X8") (pin "9") (pinfunction "9_9") (pintype "power_in"))
    )
    (net (code "21") (name "/BA1") (class "Default")
      (node (ref "U1") (pin "21") (pinfunction "BS1_21") (pintype "passive"))
      (node (ref "U2") (pin "21") (pinfunction "BS1_21") (pintype "passive"))
      (node (ref "X8") (pin "8") (pinfunction "8_8") (pintype "power_in"))
    )
    (net (code "22") (name "/D0") (class "Default")
      (node (ref "R14") (pin "2") (pinfunction "2_2") (pintype "passive"))
      (node (ref "U1") (pin "2") (pinfunction "DQ0_2") (pintype "passive"))
      (node (ref "U2") (pin "2") (pinfunction "DQ0_2") (pintype "passive"))
      (node (ref "X6") (pin "6") (pinfunction "6_6") (pintype "power_in"))
    )
    (net (code "23") (name "/D1") (class "Default")
      (node (ref "R15") (pin "2") (pinfunction "2_2") (pintype "passive"))
      (node (ref "U1") (pin "4") (pinfunction "DQ1_4") (pintype "passive"))
      (node (ref "U2") (pin "4") (pinfunction "DQ1_4") (pintype "passive"))
      (node (ref "X6") (pin "8") (pinfunction "8_8") (pintype "power_in"))
    )
    (net (code "24") (name "/D2") (class "Default")
      (node (ref "R16") (pin "2") (pinfunction "2_2") (pintype "passive"))
      (node (ref "U1") (pin "5") (pinfunction "DQ2_5") (pintype "passive"))
      (node (ref "U2") (pin "5") (pinfunction "DQ2_5") (pintype "passive"))
      (node (ref "X5") (pin "17") (pinfunction "17_17") (pintype "power_in"))
    )
    (net (code "25") (name "/D3") (class "Default")
      (node (ref "R17") (pin "2") (pinfunction "2_2") (pintype "passive"))
      (node (ref "U1") (pin "7") (pinfunction "DQ3_7") (pintype "passive"))
      (node (ref "U2") (pin "7") (pinfunction "DQ3_7") (pintype "passive"))
      (node (ref "X5") (pin "15") (pinfunction "15_15") (pintype "power_in"))
    )
    (net (code "26") (name "/D4") (class "Default")
      (node (ref "R18") (pin "2") (pinfunction "2_2") (pintype "passive"))
      (node (ref "U1") (pin "8") (pinfunction "DQ4_8") (pintype "passive"))
      (node (ref "U2") (pin "8") (pinfunction "DQ4_8") (pintype "passive"))
      (node (ref "X6") (pin "4") (pinfunction "4_4") (pintype "power_in"))
    )
    (net (code "27") (name "/D5") (class "Default")
      (node (ref "R19") (pin "2") (pinfunction "2_2") (pintype "passive"))
      (node (ref "U1") (pin "10") (pinfunction "DQ5_10") (pintype "passive"))
      (node (ref "U2") (pin "10") (pinfunction "DQ5_10") (pintype "passive"))
      (node (ref "X3") (pin "20") (pinfunction "20_20") (pintype "power_in"))
    )
    (net (code "28") (name "/D6") (class "Default")
      (node (ref "R20") (pin "2") (pinfunction "2_2") (pintype "passive"))
      (node (ref "U1") (pin "11") (pinfunction "DQ6_11") (pintype "passive"))
      (node (ref "U2") (pin "11") (pinfunction "DQ6_11") (pintype "passive"))
      (node (ref "X6") (pin "12") (pinfunction "12_12") (pintype "power_in"))
    )
    (net (code "29") (name "/D7") (class "Default")
      (node (ref "R21") (pin "2") (pinfunction "2_2") (pintype "passive"))
      (node (ref "U1") (pin "13") (pinfunction "DQ7_13") (pintype "passive"))
      (node (ref "U2") (pin "13") (pinfunction "DQ7_13") (pintype "passive"))
      (node (ref "X6") (pin "7") (pinfunction "7_7") (pintype "power_in"))
    )
    (net (code "30") (name "/D8") (class "Default")
      (node (ref "R22") (pin "2") (pinfunction "2_2") (pintype "passive"))
      (node (ref "U1") (pin "42") (pinfunction "DQ8_42") (pintype "passive"))
      (node (ref "U2") (pin "42") (pinfunction "DQ8_42") (pintype "passive"))
      (node (ref "X6") (pin "16") (pinfunction "16_16") (pintype "power_in"))
    )
    (net (code "31") (name "/D9") (class "Default")
      (node (ref "R23") (pin "2") (pinfunction "2_2") (pintype "passive"))
      (node (ref "U1") (pin "44") (pinfunction "DQ9_44") (pintype "passive"))
      (node (ref "U2") (pin "44") (pinfunction "DQ9_44") (pintype "passive"))
      (node (ref "X6") (pin "9") (pinfunction "9_9") (pintype "power_in"))
    )
    (net (code "32") (name "/D10") (class "Default")
      (node (ref "R24") (pin "2") (pinfunction "2_2") (pintype "passive"))
      (node (ref "U1") (pin "45") (pinfunction "DQ10_45") (pintype "passive"))
      (node (ref "U2") (pin "45") (pinfunction "DQ10_45") (pintype "passive"))
      (node (ref "X6") (pin "15") (pinfunction "15_15") (pintype "power_in"))
    )
    (net (code "33") (name "/D11") (class "Default")
      (node (ref "R25") (pin "2") (pinfunction "2_2") (pintype "passive"))
      (node (ref "U1") (pin "47") (pinfunction "DQ11_47") (pintype "passive"))
      (node (ref "U2") (pin "47") (pinfunction "DQ11_47") (pintype "passive"))
      (node (ref "X6") (pin "11") (pinfunction "11_11") (pintype "power_in"))
    )
    (net (code "34") (name "/D12") (class "Default")
      (node (ref "R26") (pin "2") (pinfunction "2_2") (pintype "passive"))
      (node (ref "U1") (pin "48") (pinfunction "DQ12_48") (pintype "passive"))
      (node (ref "U2") (pin "48") (pinfunction "DQ12_48") (pintype "passive"))
      (node (ref "X6") (pin "13") (pinfunction "13_13") (pintype "power_in"))
    )
    (net (code "35") (name "/D13") (class "Default")
      (node (ref "R27") (pin "2") (pinfunction "2_2") (pintype "passive"))
      (node (ref "U1") (pin "50") (pinfunction "DQ13_50") (pintype "passive"))
      (node (ref "U2") (pin "50") (pinfunction "DQ13_50") (pintype "passive"))
      (node (ref "X1") (pin "10") (pinfunction "10_10") (pintype "power_in"))
    )
    (net (code "36") (name "/D14") (class "Default")
      (node (ref "R28") (pin "2") (pinfunction "2_2") (pintype "passive"))
      (node (ref "U1") (pin "51") (pinfunction "DQ14_51") (pintype "passive"))
      (node (ref "U2") (pin "51") (pinfunction "DQ14_51") (pintype "passive"))
      (node (ref "X7") (pin "9") (pinfunction "9_9") (pintype "power_in"))
    )
    (net (code "37") (name "/D15") (class "Default")
      (node (ref "R29") (pin "2") (pinfunction "2_2") (pintype "passive"))
      (node (ref "U1") (pin "53") (pinfunction "DQ15_53") (pintype "passive"))
      (node (ref "U2") (pin "53") (pinfunction "DQ15_53") (pintype "passive"))
      (node (ref "X8") (pin "5") (pinfunction "5_5") (pintype "power_in"))
    )
    (net (code "44") (name "/LDQM") (class "Default")
      (node (ref "R1") (pin "2") (pinfunction "2_2") (pintype "passive"))
      (node (ref "U1") (pin "15") (pinfunction "LDQM_15") (pintype "passive"))
      (node (ref "U2") (pin "15") (pinfunction "LDQM_15") (pintype "passive"))
      (node (ref "X8") (pin "4") (pinfunction "4_4") (pintype "power_in"))
    )
    (net (code "45") (name "/MY_ADCON") (class "Default")
      (node (ref "SW4") (pin "S2") (pinfunction "2_S2") (pintype "passive"))
      (node (ref "X4") (pin "1") (pinfunction "1_1") (pintype "passive"))
    )
    (net (code "46") (name "/MY_AUDIO_BOOT") (class "Default")
      (node (ref "ENC1") (pin "B") (pinfunction "B_B") (pintype "passive"))
      (node (ref "X5") (pin "8") (pinfunction "8_8") (pintype "power_in"))
    )
    (net (code "47") (name "/MY_AUDIO_RST") (class "Default")
      (node (ref "ENC1") (pin "A") (pinfunction "A_A") (pintype "passive"))
      (node (ref "X5") (pin "7") (pinfunction "7_7") (pintype "power_in"))
    )
    (net (code "48") (name "/MY_CHR1") (class "Default")
      (node (ref "SW2") (pin "S2") (pinfunction "2_S2") (pintype "passive"))
      (node (ref "X8") (pin "1") (pinfunction "1_1") (pintype "passive"))
    )
    (net (code "49") (name "/MY_CHR2") (class "Default")
      (node (ref "SW1") (pin "S2") (pinfunction "2_S2") (pintype "passive"))
      (node (ref "X7") (pin "8") (pinfunction "8_8") (pintype "power_in"))
    )
    (net (code "50") (name "/MY_CHST") (class "Default")
      (node (ref "ENC1") (pin "1") (pinfunction "1_1") (pintype "passive"))
      (node (ref "SW3") (pin "S2") (pinfunction "2_S2") (pintype "passive"))
      (node (ref "X3") (pin "7") (pinfunction "7_7") (pintype "power_in"))
    )
    (net (code "51") (name "/MY_FOOT1") (class "Default")
      (node (ref "SW5") (pin "S2") (pinfunction "2_S2") (pintype "passive"))
      (node (ref "X8") (pin "7") (pinfunction "7_7") (pintype "power_in"))
    )
    (net (code "52") (name "/MY_FOOT2") (class "Default")
      (node (ref "ENC2") (pin "A") (pinfunction "A_A") (pintype "passive"))
      (node (ref "X5") (pin "4") (pinfunction "4_4") (pintype "power_in"))
    )
    (net (code "53") (name "/MY_FOOT3") (class "Default")
      (node (ref "ENC2") (pin "B") (pinfunction "B_B") (pintype "passive"))
      (node (ref "X5") (pin "2") (pinfunction "2_2") (pintype "passive"))
    )
    (net (code "54") (name "/MY_LCD_RESET") (class "Default")
      (node (ref "H1") (pin "41") (pinfunction "41_41") (pintype "passive"))
      (node (ref "R30") (pin "1") (pinfunction "1_1") (pintype "passive"))
      (node (ref "X1") (pin "4") (pinfunction "4_4") (pintype "power_in"))
    )
    (net (code "55") (name "/MY_LCD_TE_EXTI2") (class "Default")
      (node (ref "J3") (pin "2") (pinfunction "IN_2") (pintype "passive"))
      (node (ref "J4") (pin "2") (pinfunction "IN_2") (pintype "passive"))
      (node (ref "X3") (pin "2") (pinfunction "2_2") (pintype "passive"))
    )
    (net (code "56") (name "/MY_SD_DETECT") (class "Default")
      (node (ref "J1") (pin "11") (pinfunction "DETECT2_11") (pintype "bidirectional"))
      (node (ref "X3") (pin "13") (pinfunction "13_13") (pintype "power_in"))
    )
    (net (code "57") (name "/NE1") (class "Default")
      (node (ref "R10") (pin "2") (pinfunction "2_2") (pintype "passive"))
      (node (ref "X1") (pin "19") (pinfunction "19_19") (pintype "power_in"))
    )
    (net (code "58") (name "/NE4") (class "Default")
      (node (ref "X7") (pin "5") (pinfunction "5_5") (pintype "power_in"))
    )
    (net (code "59") (name "/NOE") (class "Default")
      (node (ref "R13") (pin "2") (pinfunction "2_2") (pintype "passive"))
      (node (ref "X4") (pin "19") (pinfunction "19_19") (pintype "power_in"))
    )
    (net (code "60") (name "/NWE") (class "Default")
      (node (ref "R12") (pin "2") (pinfunction "2_2") (pintype "passive"))
      (node (ref "X5") (pin "1") (pinfunction "1_1") (pintype "passive"))
    )
    (net (code "145") (name "/QUADSPI_BK1_IO0") (class "Default")
      (node (ref "IC2") (pin "5") (pinfunction "DQ0_5") (pintype "input"))
      (node (ref "X6") (pin "5") (pinfunction "5_5") (pintype "power_in"))
    )
    (net (code "146") (name "/QUADSPI_BK1_IO1") (class "Default")
      (node (ref "IC2") (pin "2") (pinfunction "DQ1_2") (pintype "output"))
      (node (ref "X6") (pin "3") (pinfunction "3_3") (pintype "power_in"))
    )
    (net (code "147") (name "/QUADSPI_BK1_IO2") (class "Default")
      (node (ref "IC2") (pin "3") (pinfunction "W#/VPP/DQ2_3") (pintype "passive"))
      (node (ref "X5") (pin "6") (pinfunction "6_6") (pintype "power_in"))
    )
    (net (code "148") (name "/QUADSPI_BK1_IO3") (class "Default")
      (node (ref "IC2") (pin "7") (pinfunction "HOLD#/DQ3_7") (pintype "passive"))
      (node (ref "X6") (pin "1") (pinfunction "1_1") (pintype "passive"))
    )
    (net (code "149") (name "/QUADSPI_BK1_NCS") (class "Default")
      (node (ref "IC2") (pin "1") (pinfunction "S#_1") (pintype "input"))
      (node (ref "X8") (pin "10") (pinfunction "10_10") (pintype "power_in"))
    )
    (net (code "150") (name "/QUADSPI_CLK") (class "Default")
      (node (ref "IC2") (pin "6") (pinfunction "C_6") (pintype "input"))
      (node (ref "X6") (pin "2") (pinfunction "2_2") (pintype "passive"))
    )
    (net (code "151") (name "/SDCKE0") (class "Default")
      (node (ref "U1") (pin "37") (pinfunction "CKE_37") (pintype "passive"))
      (node (ref "X4") (pin "17") (pinfunction "17_17") (pintype "power_in"))
    )
    (net (code "152") (name "/SDCKE1") (class "Default")
      (node (ref "U2") (pin "37") (pinfunction "CKE_37") (pintype "passive"))
      (node (ref "X3") (pin "9") (pinfunction "9_9") (pintype "power_in"))
    )
    (net (code "153") (name "/SDCLK") (class "Default")
      (node (ref "U1") (pin "38") (pinfunction "CLK_38") (pintype "passive"))
      (node (ref "U2") (pin "38") (pinfunction "CLK_38") (pintype "passive"))
      (node (ref "X8") (pin "6") (pinfunction "6_6") (pintype "power_in"))
    )
    (net (code "155") (name "/SDNCAS") (class "Default")
      (node (ref "U1") (pin "17") (pinfunction "NCAS_17") (pintype "passive"))
      (node (ref "U2") (pin "17") (pinfunction "NCAS_17") (pintype "passive"))
      (node (ref "X7") (pin "4") (pinfunction "4_4") (pintype "power_in"))
    )
    (net (code "156") (name "/SDNE0") (class "Default")
      (node (ref "U1") (pin "19") (pinfunction "NCS_19") (pintype "passive"))
      (node (ref "X4") (pin "15") (pinfunction "15_15") (pintype "power_in"))
    )
    (net (code "157") (name "/SDNE1") (class "Default")
      (node (ref "U2") (pin "19") (pinfunction "NCS_19") (pintype "passive"))
      (node (ref "X1") (pin "17") (pinfunction "17_17") (pintype "power_in"))
    )
    (net (code "158") (name "/SDNRAS") (class "Default")
      (node (ref "U1") (pin "18") (pinfunction "NRAS_18") (pintype "passive"))
      (node (ref "U2") (pin "18") (pinfunction "NRAS_18") (pintype "passive"))
      (node (ref "X8") (pin "2") (pinfunction "2_2") (pintype "passive"))
    )
    (net (code "159") (name "/SDNWE") (class "Default")
      (node (ref "U1") (pin "16") (pinfunction "NWE_16") (pintype "passive"))
      (node (ref "U2") (pin "16") (pinfunction "NWE_16") (pintype "passive"))
      (node (ref "X4") (pin "18") (pinfunction "18_18") (pintype "power_in"))
    )
    (net (code "161") (name "/SD_CK") (class "Default")
      (node (ref "J1") (pin "5") (pinfunction "CLK_5") (pintype "bidirectional"))
      (node (ref "R8") (pin "1") (pinfunction "1_1") (pintype "passive"))
      (node (ref "X2") (pin "3") (pinfunction "3_3") (pintype "power_in"))
    )
    (net (code "162") (name "/SD_CMD") (class "Default")
      (node (ref "J1") (pin "3") (pinfunction "CMD_3") (pintype "bidirectional"))
      (node (ref "R3") (pin "1") (pinfunction "1_1") (pintype "passive"))
      (node (ref "X2") (pin "4") (pinfunction "4_4") (pintype "power_in"))
    )
    (net (code "163") (name "/SD_D0") (class "Default")
      (node (ref "J1") (pin "7") (pinfunction "DAT0_7") (pintype "bidirectional"))
      (node (ref "R7") (pin "1") (pinfunction "1_1") (pintype "passive"))
      (node (ref "X1") (pin "2") (pinfunction "2_2") (pintype "passive"))
    )
    (net (code "164") (name "/SD_D1") (class "Default")
      (node (ref "J1") (pin "8") (pinfunction "DAT1_8") (pintype "bidirectional"))
      (node (ref "R6") (pin "1") (pinfunction "1_1") (pintype "passive"))
      (node (ref "X1") (pin "1") (pinfunction "1_1") (pintype "passive"))
    )
    (net (code "165") (name "/SD_D2") (class "Default")
      (node (ref "J1") (pin "1") (pinfunction "DATA2_1") (pintype "bidirectional"))
      (node (ref "R5") (pin "1") (pinfunction "1_1") (pintype "passive"))
      (node (ref "X2") (pin "1") (pinfunction "1_1") (pintype "passive"))
    )
    (net (code "166") (name "/SD_D3") (class "Default")
      (node (ref "J1") (pin "2") (pinfunction "CD/DAT3_2") (pintype "bidirectional"))
      (node (ref "R4") (pin "1") (pinfunction "1_1") (pintype "passive"))
      (node (ref "X2") (pin "2") (pinfunction "2_2") (pintype "passive"))
    )
    (net (code "167") (name "/SPI1_MISO") (class "Default")
      (node (ref "X10") (pin "1") (pinfunction "1_1") (pintype "passive"))
      (node (ref "X10") (pin "2") (pinfunction "2_2") (pintype "passive"))
      (node (ref "X7") (pin "3") (pinfunction "3_3") (pintype "power_in"))
    )
    (net (code "168") (name "/SPI1_MOSI") (class "Default")
      (node (ref "X10") (pin "3") (pinfunction "3_3") (pintype "power_in"))
      (node (ref "X10") (pin "4") (pinfunction "4_4") (pintype "power_in"))
      (node (ref "X5") (pin "5") (pinfunction "5_5") (pintype "power_in"))
    )
    (net (code "169") (name "/SPI1_NSS") (class "Default")
      (node (ref "X10") (pin "7") (pinfunction "7_7") (pintype "power_in"))
      (node (ref "X10") (pin "8") (pinfunction "8_8") (pintype "power_in"))
      (node (ref "X7") (pin "6") (pinfunction "6_6") (pintype "power_in"))
    )
    (net (code "170") (name "/SPI1_SCK") (class "Default")
      (node (ref "X10") (pin "5") (pinfunction "5_5") (pintype "power_in"))
      (node (ref "X10") (pin "6") (pinfunction "6_6") (pintype "power_in"))
      (node (ref "X7") (pin "10") (pinfunction "10_10") (pintype "power_in"))
    )
    (net (code "171") (name "/SPI2_MISO") (class "Default")
      (node (ref "X13") (pin "1") (pinfunction "1_1") (pintype "passive"))
      (node (ref "X13") (pin "2") (pinfunction "2_2") (pintype "passive"))
      (node (ref "X3") (pin "8") (pinfunction "8_8") (pintype "power_in"))
    )
    (net (code "172") (name "/SPI2_MOSI") (class "Default")
      (node (ref "X13") (pin "3") (pinfunction "3_3") (pintype "power_in"))
      (node (ref "X13") (pin "4") (pinfunction "4_4") (pintype "power_in"))
      (node (ref "X3") (pin "6") (pinfunction "6_6") (pintype "power_in"))
    )
    (net (code "173") (name "/SPI2_NSS") (class "Default")
      (node (ref "X1") (pin "16") (pinfunction "16_16") (pintype "power_in"))
      (node (ref "X13") (pin "7") (pinfunction "7_7") (pintype "power_in"))
      (node (ref "X13") (pin "8") (pinfunction "8_8") (pintype "power_in"))
    )
    (net (code "174") (name "/SPI2_SCK") (class "Default")
      (node (ref "X13") (pin "5") (pinfunction "5_5") (pintype "power_in"))
      (node (ref "X13") (pin "6") (pinfunction "6_6") (pintype "power_in"))
      (node (ref "X3") (pin "10") (pinfunction "10_10") (pintype "power_in"))
    )
    (net (code "175") (name "/TIM8_CH1N") (class "Default")
      (node (ref "X1") (pin "15") (pinfunction "15_15") (pintype "power_in"))
    )
    (net (code "176") (name "/TIM8_CH2N") (class "Default")
      (node (ref "X4") (pin "14") (pinfunction "14_14") (pintype "power_in"))
    )
    (net (code "177") (name "/TIM8_CH3N") (class "Default")
      (node (ref "SW1") (pin "3") (pinfunction "DI_3") (pintype "passive"))
      (node (ref "X3") (pin "4") (pinfunction "4_4") (pintype "power_in"))
    )
    (net (code "182") (name "/UART4_RX") (class "Default")
      (node (ref "X14") (pin "7") (pinfunction "7_7") (pintype "power_in"))
      (node (ref "X14") (pin "8") (pinfunction "8_8") (pintype "power_in"))
      (node (ref "X4") (pin "10") (pinfunction "10_10") (pintype "power_in"))
    )
    (net (code "183") (name "/UART4_TX") (class "Default")
      (node (ref "X14") (pin "5") (pinfunction "5_5") (pintype "power_in"))
      (node (ref "X14") (pin "6") (pinfunction "6_6") (pintype "power_in"))
      (node (ref "X4") (pin "8") (pinfunction "8_8") (pintype "power_in"))
    )
    (net (code "184") (name "/UDQM") (class "Default")
      (node (ref "R2") (pin "2") (pinfunction "2_2") (pintype "passive"))
      (node (ref "U1") (pin "39") (pinfunction "UDQM_39") (pintype "passive"))
      (node (ref "U2") (pin "39") (pinfunction "UDQM_39") (pintype "passive"))
      (node (ref "X7") (pin "1") (pinfunction "1_1") (pintype "passive"))
    )
    (net (code "185") (name "/USART2_RX") (class "Default")
      (node (ref "X14") (pin "3") (pinfunction "3_3") (pintype "power_in"))
      (node (ref "X14") (pin "4") (pinfunction "4_4") (pintype "power_in"))
      (node (ref "X5") (pin "3") (pinfunction "3_3") (pintype "power_in"))
    )
    (net (code "186") (name "/USART2_TX") (class "Default")
      (node (ref "X14") (pin "1") (pinfunction "1_1") (pintype "passive"))
      (node (ref "X14") (pin "2") (pinfunction "2_2") (pintype "passive"))
      (node (ref "X3") (pin "15") (pinfunction "15_15") (pintype "power_in"))
    )
    (net (code "187") (name "/USB_OTG_FS_SOF") (class "Default")
      (node (ref "TP1") (pin "1") (pinfunction "1_1") (pintype "passive"))
      (node (ref "X3") (pin "3") (pinfunction "3_3") (pintype "power_in"))
    )
    (net (code "188") (name "/VSYNC") (class "Default")
      (node (ref "H1") (pin "40") (pinfunction "40_40") (pintype "passive"))
      (node (ref "J4") (pin "1") (pinfunction "IN_1") (pintype "passive"))
    )
    (net (code "189") (name "3V_LCD") (class "Default")
      (node (ref "H1") (pin "10") (pinfunction "10_10") (pintype "passive"))
      (node (ref "H1") (pin "11") (pinfunction "11_11") (pintype "passive"))
      (node (ref "H1") (pin "45") (pinfunction "45_45") (pintype "passive"))
      (node (ref "H1") (pin "9") (pinfunction "9_9") (pintype "passive"))
      (node (ref "J6") (pin "2") (pinfunction "IN_2") (pintype "passive"))
      (node (ref "R30") (pin "2") (pinfunction "2_2") (pintype "passive"))
      (node (ref "R31") (pin "2") (pinfunction "2_2") (pintype "passive"))
      (node (ref "R32") (pin "2") (pinfunction "2_2") (pintype "passive"))
      (node (ref "R33") (pin "2") (pinfunction "2_2") (pintype "passive"))
      (node (ref "R34") (pin "2") (pinfunction "2_2") (pintype "passive"))
    )
    (net (code "190") (name "5V_USB_STLK") (class "Default")
      (node (ref "X1") (pin "8") (pinfunction "8_8") (pintype "power_in"))
    )
    (net (code "191") (name "GND") (class "Default")
      (node (ref "C1") (pin "2") (pinfunction "2_2") (pintype "passive"))
      (node (ref "C10") (pin "2") (pinfunction "2_2") (pintype "passive"))
      (node (ref "C11") (pin "2") (pinfunction "2_2") (pintype "passive"))
      (node (ref "C12") (pin "2") (pinfunction "2_2") (pintype "passive"))
      (node (ref "C13") (pin "2") (pinfunction "2_2") (pintype "passive"))
      (node (ref "C14") (pin "2") (pinfunction "2_2") (pintype "passive"))
      (node (ref "C17") (pin "1") (pinfunction "1_1") (pintype "passive"))
      (node (ref "C18") (pin "1") (pinfunction "1_1") (pintype "passive"))
      (node (ref "C19") (pin "1") (pinfunction "1_1") (pintype "passive"))
      (node (ref "C2") (pin "2") (pinfunction "2_2") (pintype "passive"))
      (node (ref "C3") (pin "2") (pinfunction "2_2") (pintype "passive"))
      (node (ref "C4") (pin "2") (pinfunction "2_2") (pintype "passive"))
      (node (ref "C5") (pin "2") (pinfunction "2_2") (pintype "passive"))
      (node (ref "C6") (pin "2") (pinfunction "2_2") (pintype "passive"))
      (node (ref "C7") (pin "2") (pinfunction "2_2") (pintype "passive"))
      (node (ref "C8") (pin "2") (pinfunction "2_2") (pintype "passive"))
      (node (ref "C9") (pin "2") (pinfunction "2_2") (pintype "passive"))
      (node (ref "ENC1") (pin "2") (pinfunction "2_2") (pintype "passive"))
      (node (ref "ENC1") (pin "C") (pinfunction "C_C") (pintype "passive"))
      (node (ref "ENC2") (pin "2") (pinfunction "2_2") (pintype "passive"))
      (node (ref "ENC2") (pin "C") (pinfunction "C_C") (pintype "passive"))
      (node (ref "H1") (pin "1") (pinfunction "1_1") (pintype "passive"))
      (node (ref "H1") (pin "2") (pinfunction "2_2") (pintype "passive"))
      (node (ref "H1") (pin "3") (pinfunction "3_3") (pintype "passive"))
      (node (ref "H1") (pin "42") (pinfunction "42_42") (pintype "passive"))
      (node (ref "H1") (pin "43") (pinfunction "43_43") (pintype "passive"))
      (node (ref "H1") (pin "44") (pinfunction "44_44") (pintype "passive"))
      (node (ref "H1") (pin "50") (pinfunction "50_50") (pintype "passive"))
      (node (ref "H1") (pin "8") (pinfunction "8_8") (pintype "passive"))
      (node (ref "IC2") (pin "4") (pinfunction "VSS_4") (pintype "power_in"))
      (node (ref "IC3") (pin "1") (pinfunction "GND_1") (pintype "input"))
      (node (ref "J1") (pin "10") (pinfunction "GND_2_10") (pintype "passive"))
      (node (ref "J1") (pin "12") (pinfunction "DETECT1_12") (pintype "bidirectional"))
      (node (ref "J1") (pin "6") (pinfunction "VSS_6") (pintype "power_in"))
      (node (ref "J1") (pin "9") (pinfunction "GND_1_9") (pintype "passive"))
      (node (ref "R1") (pin "1") (pinfunction "1_1") (pintype "passive"))
      (node (ref "R2") (pin "1") (pinfunction "1_1") (pintype "passive"))
      (node (ref "R37") (pin "1") (pinfunction "1_1") (pintype "passive"))
      (node (ref "R37") (pin "4") (pinfunction "4_4") (pintype "passive"))
      (node (ref "R38") (pin "1") (pinfunction "1_1") (pintype "passive"))
      (node (ref "SW1") (pin "2") (pinfunction "GND_2") (pintype "passive"))
      (node (ref "SW1") (pin "S1") (pinfunction "1_S1") (pintype "passive"))
      (node (ref "SW2") (pin "2") (pinfunction "GND_2") (pintype "passive"))
      (node (ref "SW2") (pin "S1") (pinfunction "1_S1") (pintype "passive"))
      (node (ref "SW3") (pin "2") (pinfunction "GND_2") (pintype "passive"))
      (node (ref "SW3") (pin "S1") (pinfunction "1_S1") (pintype "passive"))
      (node (ref "SW4") (pin "2") (pinfunction "GND_2") (pintype "passive"))
      (node (ref "SW4") (pin "S1") (pinfunction "1_S1") (pintype "passive"))
      (node (ref "SW5") (pin "S1") (pinfunction "1_S1") (pintype "passive"))
      (node (ref "U1") (pin "12") (pinfunction "VSSQ_12") (pintype "passive"))
      (node (ref "U1") (pin "28") (pinfunction "VSS_28") (pintype "passive"))
      (node (ref "U1") (pin "41") (pinfunction "VSS_41") (pintype "passive"))
      (node (ref "U1") (pin "46") (pinfunction "VSSQ_46") (pintype "passive"))
      (node (ref "U1") (pin "52") (pinfunction "VSSQ_52") (pintype "passive"))
      (node (ref "U1") (pin "54") (pinfunction "VSS_54") (pintype "passive"))
      (node (ref "U1") (pin "6") (pinfunction "VSSQ_6") (pintype "passive"))
      (node (ref "U2") (pin "12") (pinfunction "VSSQ_12") (pintype "passive"))
      (node (ref "U2") (pin "28") (pinfunction "VSS_28") (pintype "passive"))
      (node (ref "U2") (pin "41") (pinfunction "VSS_41") (pintype "passive"))
      (node (ref "U2") (pin "46") (pinfunction "VSSQ_46") (pintype "passive"))
      (node (ref "U2") (pin "52") (pinfunction "VSSQ_52") (pintype "passive"))
      (node (ref "U2") (pin "54") (pinfunction "VSS_54") (pintype "passive"))
      (node (ref "U2") (pin "6") (pinfunction "VSSQ_6") (pintype "passive"))
      (node (ref "X1") (pin "20") (pinfunction "20_20") (pintype "power_in"))
      (node (ref "X1") (pin "9") (pinfunction "9_9") (pintype "power_in"))
      (node (ref "X11") (pin "1") (pinfunction "1_1") (pintype "passive"))
      (node (ref "X11") (pin "2") (pinfunction "2_2") (pintype "passive"))
      (node (ref "X12") (pin "1") (pinfunction "1_1") (pintype "passive"))
      (node (ref "X12") (pin "2") (pinfunction "2_2") (pintype "passive"))
      (node (ref "X2") (pin "19") (pinfunction "19_19") (pintype "power_in"))
      (node (ref "X2") (pin "20") (pinfunction "20_20") (pintype "power_in"))
      (node (ref "X2") (pin "8") (pinfunction "8_8") (pintype "power_in"))
      (node (ref "X3") (pin "19") (pinfunction "19_19") (pintype "power_in"))
      (node (ref "X4") (pin "2") (pinfunction "2_2") (pintype "passive"))
      (node (ref "X5") (pin "20") (pinfunction "20_20") (pintype "power_in"))
      (node (ref "X5") (pin "9") (pinfunction "9_9") (pintype "power_in"))
      (node (ref "X6") (pin "14") (pinfunction "14_14") (pintype "power_in"))
      (node (ref "X8") (pin "3") (pinfunction "3_3") (pintype "power_in"))
      (node (ref "X9") (pin "1") (pinfunction "1_1") (pintype "passive"))
      (node (ref "X9") (pin "2") (pinfunction "2_2") (pintype "passive"))
    )
    (net (code "192") (name "Net-(H1-Pad12)") (class "Default")
      (node (ref "H1") (pin "12") (pinfunction "12_12") (pintype "passive"))
      (node (ref "R9") (pin "1") (pinfunction "1_1") (pintype "passive"))
    )
    (net (code "193") (name "Net-(H1-Pad13)") (class "Default")
      (node (ref "H1") (pin "13") (pinfunction "13_13") (pintype "passive"))
      (node (ref "R10") (pin "1") (pinfunction "1_1") (pintype "passive"))
    )
    (net (code "194") (name "Net-(H1-Pad14)") (class "Default")
      (node (ref "H1") (pin "14") (pinfunction "14_14") (pintype "passive"))
      (node (ref "R11") (pin "1") (pinfunction "1_1") (pintype "passive"))
    )
    (net (code "195") (name "Net-(H1-Pad15)") (class "Default")
      (node (ref "H1") (pin "15") (pinfunction "15_15") (pintype "passive"))
      (node (ref "R12") (pin "1") (pinfunction "1_1") (pintype "passive"))
    )
    (net (code "196") (name "Net-(H1-Pad16)") (class "Default")
      (node (ref "H1") (pin "16") (pinfunction "16_16") (pintype "passive"))
      (node (ref "R13") (pin "1") (pinfunction "1_1") (pintype "passive"))
    )
    (net (code "197") (name "Net-(H1-Pad19)") (class "Default")
      (node (ref "H1") (pin "19") (pinfunction "19_19") (pintype "passive"))
      (node (ref "R14") (pin "1") (pinfunction "1_1") (pintype "passive"))
    )
    (net (code "198") (name "Net-(H1-Pad20)") (class "Default")
      (node (ref "H1") (pin "20") (pinfunction "20_20") (pintype "passive"))
      (node (ref "R15") (pin "1") (pinfunction "1_1") (pintype "passive"))
    )
    (net (code "199") (name "Net-(H1-Pad21)") (class "Default")
      (node (ref "H1") (pin "21") (pinfunction "21_21") (pintype "passive"))
      (node (ref "R16") (pin "1") (pinfunction "1_1") (pintype "passive"))
    )
    (net (code "200") (name "Net-(H1-Pad22)") (class "Default")
      (node (ref "H1") (pin "22") (pinfunction "22_22") (pintype "passive"))
      (node (ref "R17") (pin "1") (pinfunction "1_1") (pintype "passive"))
    )
    (net (code "201") (name "Net-(H1-Pad23)") (class "Default")
      (node (ref "H1") (pin "23") (pinfunction "23_23") (pintype "passive"))
      (node (ref "R18") (pin "1") (pinfunction "1_1") (pintype "passive"))
    )
    (net (code "202") (name "Net-(H1-Pad24)") (class "Default")
      (node (ref "H1") (pin "24") (pinfunction "24_24") (pintype "passive"))
      (node (ref "R19") (pin "1") (pinfunction "1_1") (pintype "passive"))
    )
    (net (code "203") (name "Net-(H1-Pad25)") (class "Default")
      (node (ref "H1") (pin "25") (pinfunction "25_25") (pintype "passive"))
      (node (ref "R20") (pin "1") (pinfunction "1_1") (pintype "passive"))
    )
    (net (code "204") (name "Net-(H1-Pad26)") (class "Default")
      (node (ref "H1") (pin "26") (pinfunction "26_26") (pintype "passive"))
      (node (ref "R21") (pin "1") (pinfunction "1_1") (pintype "passive"))
    )
    (net (code "205") (name "Net-(H1-Pad27)") (class "Default")
      (node (ref "H1") (pin "27") (pinfunction "27_27") (pintype "passive"))
      (node (ref "R22") (pin "1") (pinfunction "1_1") (pintype "passive"))
    )
    (net (code "206") (name "Net-(H1-Pad28)") (class "Default")
      (node (ref "H1") (pin "28") (pinfunction "28_28") (pintype "passive"))
      (node (ref "R23") (pin "1") (pinfunction "1_1") (pintype "passive"))
    )
    (net (code "207") (name "Net-(H1-Pad29)") (class "Default")
      (node (ref "H1") (pin "29") (pinfunction "29_29") (pintype "passive"))
      (node (ref "R24") (pin "1") (pinfunction "1_1") (pintype "passive"))
    )
    (net (code "208") (name "Net-(H1-Pad30)") (class "Default")
      (node (ref "H1") (pin "30") (pinfunction "30_30") (pintype "passive"))
      (node (ref "R25") (pin "1") (pinfunction "1_1") (pintype "passive"))
    )
    (net (code "209") (name "Net-(H1-Pad31)") (class "Default")
      (node (ref "H1") (pin "31") (pinfunction "31_31") (pintype "passive"))
      (node (ref "R26") (pin "1") (pinfunction "1_1") (pintype "passive"))
    )
    (net (code "210") (name "Net-(H1-Pad32)") (class "Default")
      (node (ref "H1") (pin "32") (pinfunction "32_32") (pintype "passive"))
      (node (ref "R27") (pin "1") (pinfunction "1_1") (pintype "passive"))
    )
    (net (code "211") (name "Net-(H1-Pad33)") (class "Default")
      (node (ref "H1") (pin "33") (pinfunction "33_33") (pintype "passive"))
      (node (ref "R28") (pin "1") (pinfunction "1_1") (pintype "passive"))
    )
    (net (code "212") (name "Net-(H1-Pad34)") (class "Default")
      (node (ref "H1") (pin "34") (pinfunction "34_34") (pintype "passive"))
      (node (ref "R29") (pin "1") (pinfunction "1_1") (pintype "passive"))
    )
    (net (code "213") (name "Net-(H1-Pad46)") (class "Default")
      (node (ref "H1") (pin "46") (pinfunction "46_46") (pintype "passive"))
      (node (ref "R31") (pin "1") (pinfunction "1_1") (pintype "passive"))
    )
    (net (code "214") (name "Net-(H1-Pad47)") (class "Default")
      (node (ref "H1") (pin "47") (pinfunction "47_47") (pintype "passive"))
      (node (ref "R32") (pin "1") (pinfunction "1_1") (pintype "passive"))
    )
    (net (code "215") (name "Net-(H1-Pad48)") (class "Default")
      (node (ref "H1") (pin "48") (pinfunction "48_48") (pintype "passive"))
      (node (ref "R33") (pin "1") (pinfunction "1_1") (pintype "passive"))
    )
    (net (code "216") (name "Net-(H1-Pad49)") (class "Default")
      (node (ref "H1") (pin "49") (pinfunction "49_49") (pintype "passive"))
      (node (ref "R34") (pin "1") (pinfunction "1_1") (pintype "passive"))
    )
    (net (code "217") (name "Net-(J3-IN-Pad1)") (class "Default")
      (node (ref "J3") (pin "1") (pinfunction "IN_1") (pintype "passive"))
      (node (ref "R9") (pin "2") (pinfunction "2_2") (pintype "passive"))
    )
    (net (code "218") (name "Net-(R35-Pad1)") (class "Default")
      (node (ref "R35") (pin "1") (pinfunction "1_1") (pintype "passive"))
      (node (ref "R36") (pin "1") (pinfunction "1_1") (pintype "passive"))
      (node (ref "R37") (pin "3") (pinfunction "3_3") (pintype "passive"))
      (node (ref "R38") (pin "2") (pinfunction "2_2") (pintype "passive"))
    )
    (net (code "219") (name "Net-(SW1B-DO)") (class "Default")
      (node (ref "SW1") (pin "1") (pinfunction "DO_1") (pintype "passive"))
      (node (ref "SW2") (pin "3") (pinfunction "DI_3") (pintype "passive"))
    )
    (net (code "220") (name "Net-(SW2B-DO)") (class "Default")
      (node (ref "SW2") (pin "1") (pinfunction "DO_1") (pintype "passive"))
      (node (ref "SW4") (pin "3") (pinfunction "DI_3") (pintype "passive"))
    )
    (net (code "221") (name "Net-(SW3B-DI)") (class "Default")
      (node (ref "SW3") (pin "3") (pinfunction "DI_3") (pintype "passive"))
      (node (ref "SW4") (pin "1") (pinfunction "DO_1") (pintype "passive"))
    )
    (net (code "222") (name "Net-(SW3B-VDD)") (class "Default")
      (node (ref "J5") (pin "2") (pinfunction "IN_2") (pintype "passive"))
      (node (ref "SW3") (pin "4") (pinfunction "VDD_4") (pintype "passive"))
    )
    (net (code "223") (name "unconnected-(ENC1-PadMT1)") (class "Default")
      (node (ref "ENC1") (pin "MT1") (pinfunction "MT1_MT1") (pintype "passive"))
    )
    (net (code "224") (name "unconnected-(ENC1-PadMT2)") (class "Default")
      (node (ref "ENC1") (pin "MT2") (pinfunction "MT2_MT2") (pintype "passive"))
    )
    (net (code "225") (name "unconnected-(ENC2-Pad1)") (class "Default")
      (node (ref "ENC2") (pin "1") (pinfunction "1_1") (pintype "passive"))
    )
    (net (code "226") (name "unconnected-(ENC2-PadMT1)") (class "Default")
      (node (ref "ENC2") (pin "MT1") (pinfunction "MT1_MT1") (pintype "passive"))
    )
    (net (code "227") (name "unconnected-(ENC2-PadMT2)") (class "Default")
      (node (ref "ENC2") (pin "MT2") (pinfunction "MT2_MT2") (pintype "passive"))
    )
    (net (code "228") (name "unconnected-(H1-Pad4)") (class "Default")
      (node (ref "H1") (pin "4") (pinfunction "4_4") (pintype "passive"))
    )
    (net (code "229") (name "unconnected-(H1-Pad5)") (class "Default")
      (node (ref "H1") (pin "5") (pinfunction "5_5") (pintype "passive"))
    )
    (net (code "230") (name "unconnected-(H1-Pad6)") (class "Default")
      (node (ref "H1") (pin "6") (pinfunction "6_6") (pintype "passive"))
    )
    (net (code "231") (name "unconnected-(H1-Pad7)") (class "Default")
      (node (ref "H1") (pin "7") (pinfunction "7_7") (pintype "passive"))
    )
    (net (code "232") (name "unconnected-(H1-Pad17)") (class "Default")
      (node (ref "H1") (pin "17") (pinfunction "17_17") (pintype "passive"))
    )
    (net (code "233") (name "unconnected-(H1-Pad18)") (class "Default")
      (node (ref "H1") (pin "18") (pinfunction "18_18") (pintype "passive"))
    )
    (net (code "234") (name "unconnected-(H1-Pad35)") (class "Default")
      (node (ref "H1") (pin "35") (pinfunction "35_35") (pintype "passive"))
    )
    (net (code "235") (name "unconnected-(H1-Pad36)") (class "Default")
      (node (ref "H1") (pin "36") (pinfunction "36_36") (pintype "passive"))
    )
    (net (code "236") (name "unconnected-(H1-Pad37)") (class "Default")
      (node (ref "H1") (pin "37") (pinfunction "37_37") (pintype "passive"))
    )
    (net (code "237") (name "unconnected-(H1-Pad38)") (class "Default")
      (node (ref "H1") (pin "38") (pinfunction "38_38") (pintype "passive"))
    )
    (net (code "238") (name "unconnected-(H1-Pad39)") (class "Default")
      (node (ref "H1") (pin "39") (pinfunction "39_39") (pintype "passive"))
    )
    (net (code "239") (name "unconnected-(J1-SHIELD-PadMP1)") (class "Default")
      (node (ref "J1") (pin "MP1") (pinfunction "SHIELD_MP1") (pintype "passive"))
    )
    (net (code "240") (name "unconnected-(J1-SHIELD-PadMP2)") (class "Default")
      (node (ref "J1") (pin "MP2") (pinfunction "SHIELD_MP2") (pintype "passive"))
    )
    (net (code "241") (name "unconnected-(J1-SHIELD-PadMP3)") (class "Default")
      (node (ref "J1") (pin "MP3") (pinfunction "SHIELD_MP3") (pintype "passive"))
    )
    (net (code "242") (name "unconnected-(J1-SHIELD-PadMP4)") (class "Default")
      (node (ref "J1") (pin "MP4") (pinfunction "SHIELD_MP4") (pintype "passive"))
    )
    (net (code "243") (name "unconnected-(SW3B-DO-Pad1)") (class "Default")
      (node (ref "SW3") (pin "1") (pinfunction "DO_1") (pintype "passive"))
    )
    (net (code "244") (name "unconnected-(U1-NC-Pad36)") (class "Default")
      (node (ref "U1") (pin "36") (pinfunction "NC_36") (pintype "passive"))
    )
    (net (code "245") (name "unconnected-(U1-NC-Pad40)") (class "Default")
      (node (ref "U1") (pin "40") (pinfunction "NC_40") (pintype "passive"))
    )
    (net (code "246") (name "unconnected-(U2-NC-Pad36)") (class "Default")
      (node (ref "U2") (pin "36") (pinfunction "NC_36") (pintype "passive"))
    )
    (net (code "247") (name "unconnected-(U2-NC-Pad40)") (class "Default")
      (node (ref "U2") (pin "40") (pinfunction "NC_40") (pintype "passive"))
    )
    (net (code "248") (name "unconnected-(X1-Pad3)") (class "Default")
      (node (ref "X1") (pin "3") (pinfunction "3_3") (pintype "power_in"))
    )
    (net (code "249") (name "unconnected-(X1-Pad5)") (class "Default")
      (node (ref "X1") (pin "5") (pinfunction "5_5") (pintype "power_in"))
    )
    (net (code "250") (name "unconnected-(X1-Pad6)") (class "Default")
      (node (ref "X1") (pin "6") (pinfunction "6_6") (pintype "power_in"))
    )
    (net (code "251") (name "unconnected-(X1-Pad7)") (class "Default")
      (node (ref "X1") (pin "7") (pinfunction "7_7") (pintype "power_in"))
    )
    (net (code "252") (name "unconnected-(X1-Pad11)") (class "Default")
      (node (ref "X1") (pin "11") (pinfunction "11_11") (pintype "power_in"))
    )
    (net (code "253") (name "unconnected-(X1-Pad12)") (class "Default")
      (node (ref "X1") (pin "12") (pinfunction "12_12") (pintype "power_in"))
    )
    (net (code "254") (name "unconnected-(X1-Pad14)") (class "Default")
      (node (ref "X1") (pin "14") (pinfunction "14_14") (pintype "power_in"))
    )
    (net (code "255") (name "unconnected-(X1-Pad18)") (class "Default")
      (node (ref "X1") (pin "18") (pinfunction "18_18") (pintype "power_in"))
    )
    (net (code "256") (name "unconnected-(X2-Pad5)") (class "Default")
      (node (ref "X2") (pin "5") (pinfunction "5_5") (pintype "power_in"))
    )
    (net (code "257") (name "unconnected-(X2-Pad6)") (class "Default")
      (node (ref "X2") (pin "6") (pinfunction "6_6") (pintype "power_in"))
    )
    (net (code "258") (name "unconnected-(X2-Pad7)") (class "Default")
      (node (ref "X2") (pin "7") (pinfunction "7_7") (pintype "power_in"))
    )
    (net (code "259") (name "unconnected-(X2-Pad9)") (class "Default")
      (node (ref "X2") (pin "9") (pinfunction "9_9") (pintype "power_in"))
    )
    (net (code "260") (name "unconnected-(X2-Pad10)") (class "Default")
      (node (ref "X2") (pin "10") (pinfunction "10_10") (pintype "power_in"))
    )
    (net (code "261") (name "unconnected-(X2-Pad11)") (class "Default")
      (node (ref "X2") (pin "11") (pinfunction "11_11") (pintype "power_in"))
    )
    (net (code "262") (name "unconnected-(X2-Pad12)") (class "Default")
      (node (ref "X2") (pin "12") (pinfunction "12_12") (pintype "power_in"))
    )
    (net (code "263") (name "unconnected-(X2-Pad13)") (class "Default")
      (node (ref "X2") (pin "13") (pinfunction "13_13") (pintype "power_in"))
    )
    (net (code "264") (name "unconnected-(X2-Pad14)") (class "Default")
      (node (ref "X2") (pin "14") (pinfunction "14_14") (pintype "power_in"))
    )
    (net (code "265") (name "unconnected-(X2-Pad15)") (class "Default")
      (node (ref "X2") (pin "15") (pinfunction "15_15") (pintype "power_in"))
    )
    (net (code "266") (name "unconnected-(X2-Pad18)") (class "Default")
      (node (ref "X2") (pin "18") (pinfunction "18_18") (pintype "power_in"))
    )
    (net (code "267") (name "unconnected-(X3-Pad1)") (class "Default")
      (node (ref "X3") (pin "1") (pinfunction "1_1") (pintype "passive"))
    )
    (net (code "268") (name "unconnected-(X3-Pad5)") (class "Default")
      (node (ref "X3") (pin "5") (pinfunction "5_5") (pintype "power_in"))
    )
    (net (code "269") (name "unconnected-(X3-Pad11)") (class "Default")
      (node (ref "X3") (pin "11") (pinfunction "11_11") (pintype "power_in"))
    )
    (net (code "270") (name "unconnected-(X3-Pad12)") (class "Default")
      (node (ref "X3") (pin "12") (pinfunction "12_12") (pintype "power_in"))
    )
    (net (code "271") (name "unconnected-(X3-Pad14)") (class "Default")
      (node (ref "X3") (pin "14") (pinfunction "14_14") (pintype "power_in"))
    )
    (net (code "272") (name "unconnected-(X3-Pad17)") (class "Default")
      (node (ref "X3") (pin "17") (pinfunction "17_17") (pintype "power_in"))
    )
    (net (code "273") (name "unconnected-(X4-Pad3)") (class "Default")
      (node (ref "X4") (pin "3") (pinfunction "3_3") (pintype "power_in"))
    )
    (net (code "274") (name "unconnected-(X4-Pad4)") (class "Default")
      (node (ref "X4") (pin "4") (pinfunction "4_4") (pintype "power_in"))
    )
    (net (code "275") (name "unconnected-(X4-Pad5)") (class "Default")
      (node (ref "X4") (pin "5") (pinfunction "5_5") (pintype "power_in"))
    )
    (net (code "276") (name "unconnected-(X4-Pad6)") (class "Default")
      (node (ref "X4") (pin "6") (pinfunction "6_6") (pintype "power_in"))
    )
    (net (code "277") (name "unconnected-(X4-Pad7)") (class "Default")
      (node (ref "X4") (pin "7") (pinfunction "7_7") (pintype "power_in"))
    )
    (net (code "278") (name "unconnected-(X4-Pad9)") (class "Default")
      (node (ref "X4") (pin "9") (pinfunction "9_9") (pintype "power_in"))
    )
    (net (code "279") (name "unconnected-(X4-Pad11)") (class "Default")
      (node (ref "X4") (pin "11") (pinfunction "11_11") (pintype "power_in"))
    )
    (net (code "280") (name "unconnected-(X4-Pad12)") (class "Default")
      (node (ref "X4") (pin "12") (pinfunction "12_12") (pintype "power_in"))
    )
    (net (code "281") (name "unconnected-(X4-Pad13)") (class "Default")
      (node (ref "X4") (pin "13") (pinfunction "13_13") (pintype "power_in"))
    )
    (net (code "282") (name "unconnected-(X4-Pad16)") (class "Default")
      (node (ref "X4") (pin "16") (pinfunction "16_16") (pintype "power_in"))
    )
    (net (code "283") (name "unconnected-(X4-Pad20)") (class "Default")
      (node (ref "X4") (pin "20") (pinfunction "20_20") (pintype "power_in"))
    )
    (net (code "284") (name "unconnected-(X5-Pad14)") (class "Default")
      (node (ref "X5") (pin "14") (pinfunction "14_14") (pintype "power_in"))
    )
    (net (code "285") (name "unconnected-(X5-Pad16)") (class "Default")
      (node (ref "X5") (pin "16") (pinfunction "16_16") (pintype "power_in"))
    )
    (net (code "286") (name "unconnected-(X7-Pad7)") (class "Default")
      (node (ref "X7") (pin "7") (pinfunction "7_7") (pintype "power_in"))
    )
    (net (code "287") (name "unconnected-(X7-Pad11)") (class "Default")
      (node (ref "X7") (pin "11") (pinfunction "11_11") (pintype "power_in"))
    )
    (net (code "288") (name "unconnected-(X7-Pad12)") (class "Default")
      (node (ref "X7") (pin "12") (pinfunction "12_12") (pintype "power_in"))
    )
    (net (code "289") (name "unconnected-(X7-Pad13)") (class "Default")
      (node (ref "X7") (pin "13") (pinfunction "13_13") (pintype "power_in"))
    )
    (net (code "290") (name "unconnected-(X7-Pad14)") (class "Default")
      (node (ref "X7") (pin "14") (pinfunction "14_14") (pintype "power_in"))
    )
    (net (code "291") (name "unconnected-(X7-Pad15)") (class "Default")
      (node (ref "X7") (pin "15") (pinfunction "15_15") (pintype "power_in"))
    )
    (net (code "292") (name "unconnected-(X7-Pad16)") (class "Default")
      (node (ref "X7") (pin "16") (pinfunction "16_16") (pintype "power_in"))
    )
    (net (code "293") (name "unconnected-(X7-Pad17)") (class "Default")
      (node (ref "X7") (pin "17") (pinfunction "17_17") (pintype "power_in"))
    )
    (net (code "294") (name "unconnected-(X7-Pad18)") (class "Default")
      (node (ref "X7") (pin "18") (pinfunction "18_18") (pintype "power_in"))
    )
    (net (code "295") (name "unconnected-(X7-Pad19)") (class "Default")
      (node (ref "X7") (pin "19") (pinfunction "19_19") (pintype "power_in"))
    )
    (net (code "296") (name "unconnected-(X7-Pad20)") (class "Default")
      (node (ref "X7") (pin "20") (pinfunction "20_20") (pintype "power_in"))
    )
    (net (code "297") (name "unconnected-(X8-Pad11)") (class "Default")
      (node (ref "X8") (pin "11") (pinfunction "11_11") (pintype "power_in"))
    )
    (net (code "298") (name "unconnected-(X8-Pad12)") (class "Default")
      (node (ref "X8") (pin "12") (pinfunction "12_12") (pintype "power_in"))
    )
    (net (code "299") (name "unconnected-(X8-Pad13)") (class "Default")
      (node (ref "X8") (pin "13") (pinfunction "13_13") (pintype "power_in"))
    )
    (net (code "300") (name "unconnected-(X8-Pad14)") (class "Default")
      (node (ref "X8") (pin "14") (pinfunction "14_14") (pintype "power_in"))
    )
    (net (code "301") (name "unconnected-(X8-Pad15)") (class "Default")
      (node (ref "X8") (pin "15") (pinfunction "15_15") (pintype "power_in"))
    )
    (net (code "302") (name "unconnected-(X8-Pad16)") (class "Default")
      (node (ref "X8") (pin "16") (pinfunction "16_16") (pintype "power_in"))
    )
    (net (code "303") (name "unconnected-(X8-Pad17)") (class "Default")
      (node (ref "X8") (pin "17") (pinfunction "17_17") (pintype "power_in"))
    )
    (net (code "304") (name "unconnected-(X8-Pad18)") (class "Default")
      (node (ref "X8") (pin "18") (pinfunction "18_18") (pintype "power_in"))
    )
    (net (code "305") (name "unconnected-(X8-Pad19)") (class "Default")
      (node (ref "X8") (pin "19") (pinfunction "19_19") (pintype "power_in"))
    )
    (net (code "306") (name "unconnected-(X8-Pad20)") (class "Default")
      (node (ref "X8") (pin "20") (pinfunction "20_20") (pintype "power_in"))
    )
  )
)
